# EtherMegaR3.net
KiCad netlist of a schematic drawn in EAGLE
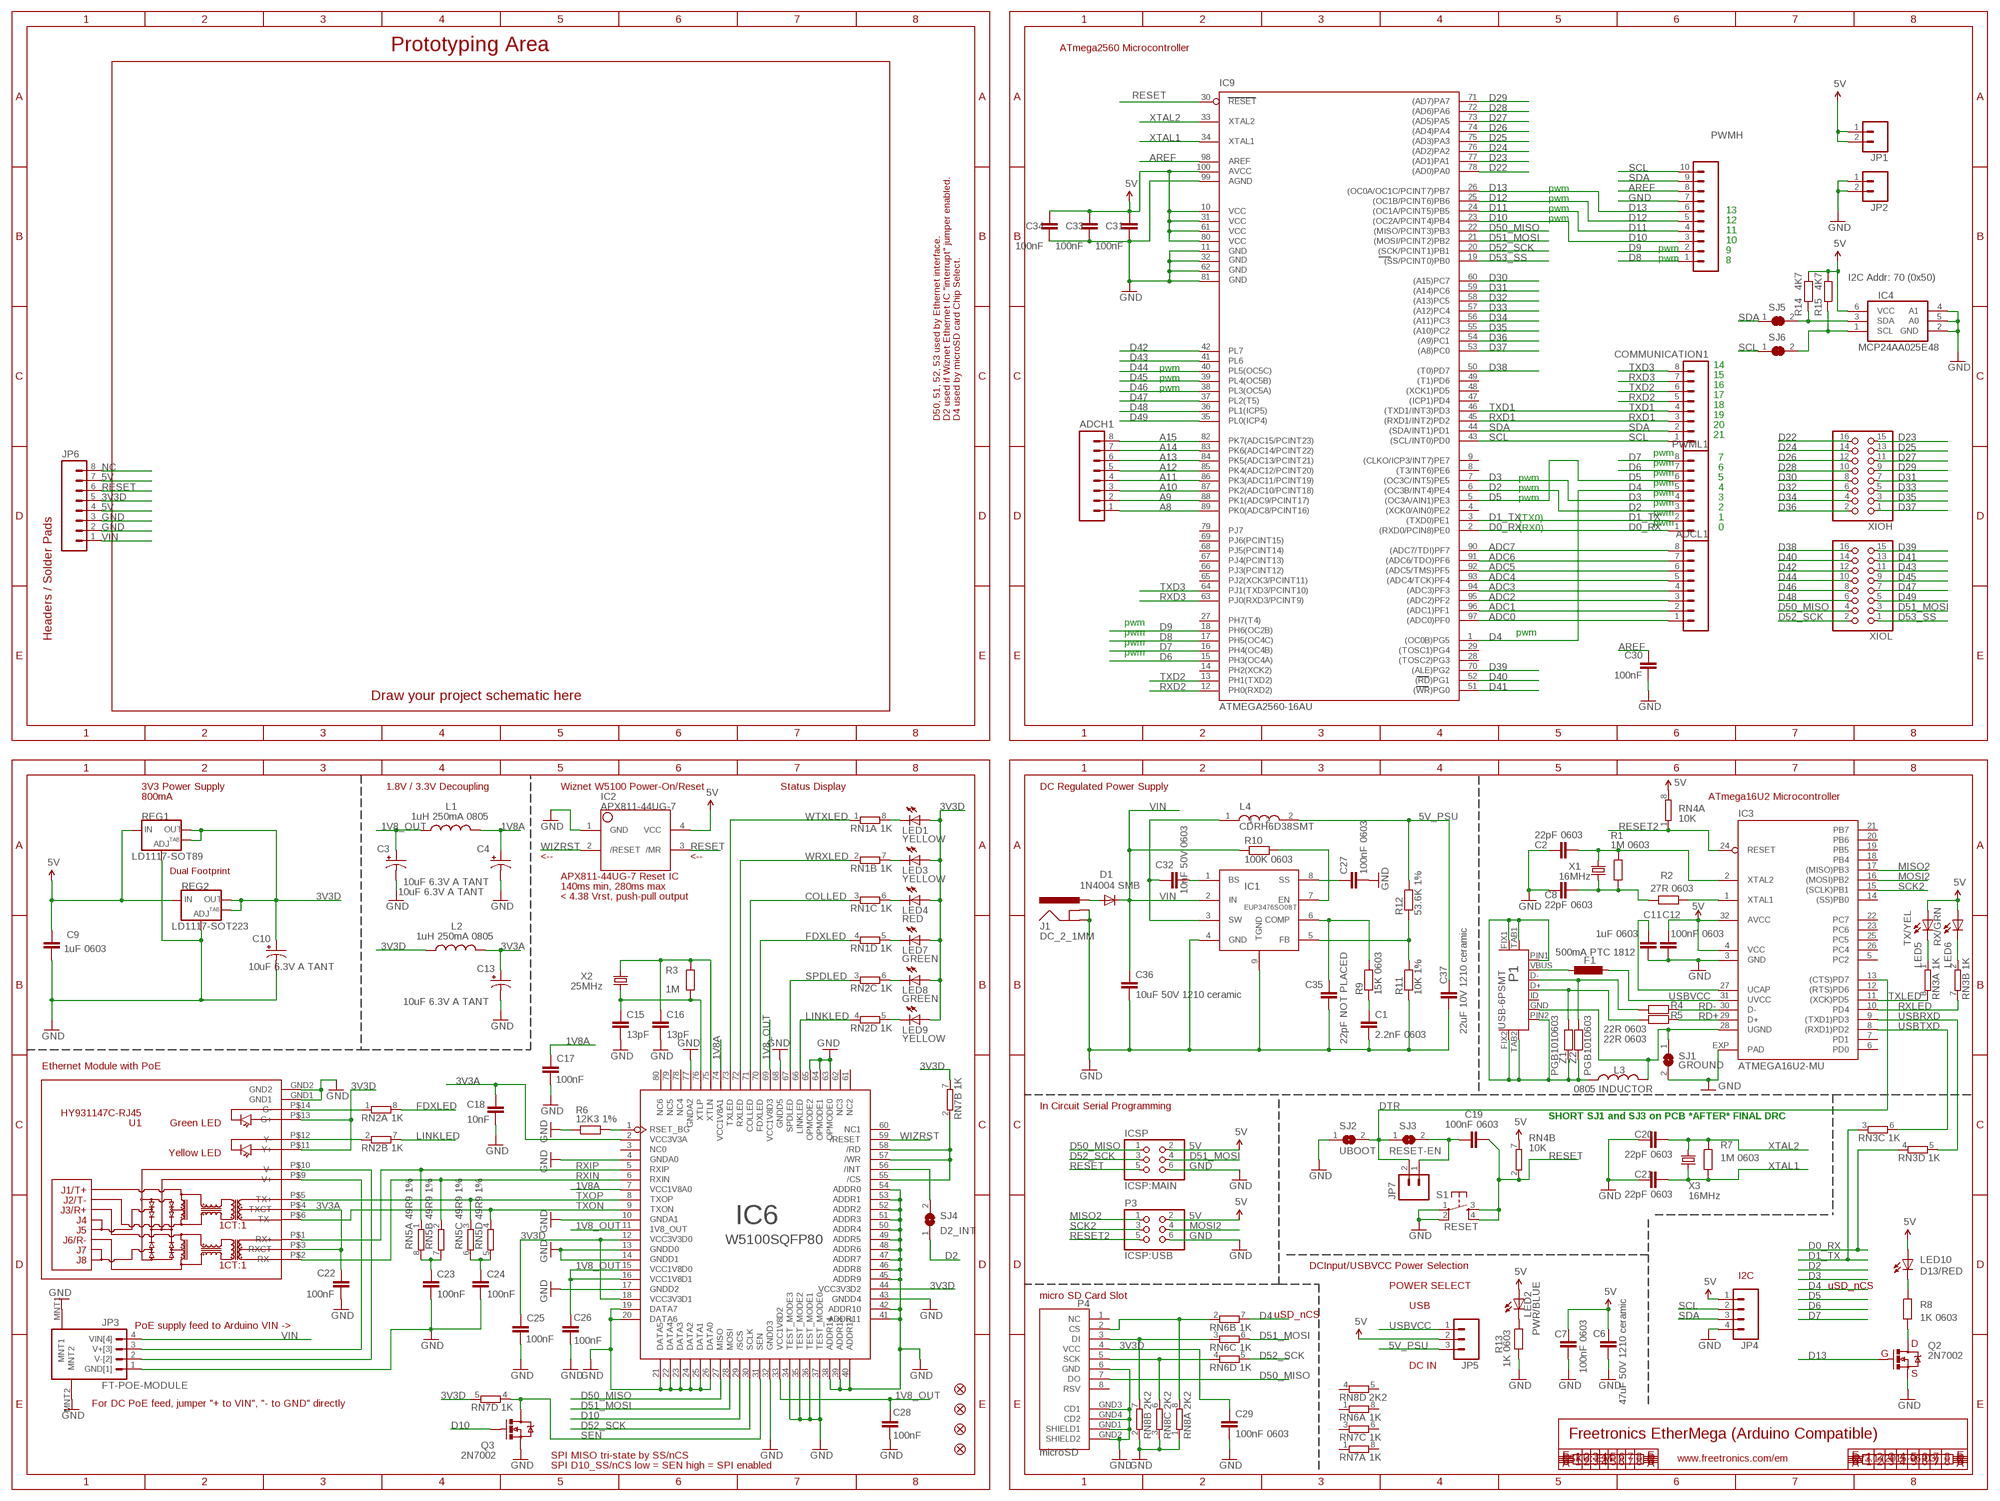
[diagram p0: schematic, sheet 1]

(export (version "E")
  (design (tool "Eeschema 10.0.6"))
  (components
    (comp (ref "ADCH1")
      (value "M08STD")
      (footprint "eagle-import:1X08")
      (libsource (lib "eagle-import") (part "M08STD"))
    )
    (comp (ref "ADCL1")
      (value "M08STD")
      (footprint "eagle-import:1X08")
      (libsource (lib "eagle-import") (part "M08STD"))
    )
    (comp (ref "C1")
      (value "2.2nF 0603")
      (footprint "eagle-import:0603")
      (libsource (lib "eagle-import") (part "CAP0603"))
    )
    (comp (ref "C2")
      (value "22pF 0603")
      (footprint "eagle-import:0603")
      (libsource (lib "eagle-import") (part "CAP0603"))
    )
    (comp (ref "C3")
      (value "10uF 6.3V A TANT")
      (footprint "eagle-import:EIA3216")
      (libsource (lib "eagle-import") (part "CAP_POL1206"))
    )
    (comp (ref "C4")
      (value "10uF 6.3V A TANT")
      (footprint "eagle-import:EIA3216")
      (libsource (lib "eagle-import") (part "CAP_POL1206"))
    )
    (comp (ref "C6")
      (value "47uF 50V 1210 ceramic")
      (footprint "eagle-import:C1210")
      (libsource (lib "eagle-import") (part "C-EUC1210"))
    )
    (comp (ref "C7")
      (value "100nF 0603")
      (footprint "eagle-import:0603")
      (libsource (lib "eagle-import") (part "CAP0603"))
    )
    (comp (ref "C8")
      (value "22pF 0603")
      (footprint "eagle-import:0603")
      (libsource (lib "eagle-import") (part "CAP0603"))
    )
    (comp (ref "C9")
      (value "1uF 0603")
      (footprint "eagle-import:0603")
      (libsource (lib "eagle-import") (part "CAP0603"))
    )
    (comp (ref "C10")
      (value "10uF 6.3V A TANT")
      (footprint "eagle-import:EIA3216")
      (libsource (lib "eagle-import") (part "CAP_POL1206"))
    )
    (comp (ref "C11")
      (value "1uF 0603")
      (footprint "eagle-import:0603")
      (libsource (lib "eagle-import") (part "freetronics-master-v1_CAP0603"))
    )
    (comp (ref "C12")
      (value "100nF 0603")
      (footprint "eagle-import:0603")
      (libsource (lib "eagle-import") (part "CAP0603"))
    )
    (comp (ref "C13")
      (value "10uF 6.3V A TANT")
      (footprint "eagle-import:EIA3216")
      (libsource (lib "eagle-import") (part "CAP_POL1206"))
    )
    (comp (ref "C15")
      (value "13pF")
      (footprint "eagle-import:0603")
      (libsource (lib "eagle-import") (part "CAP0603"))
    )
    (comp (ref "C16")
      (value "13pF")
      (footprint "eagle-import:0603")
      (libsource (lib "eagle-import") (part "CAP0603"))
    )
    (comp (ref "C17")
      (value "100nF")
      (footprint "eagle-import:0603")
      (libsource (lib "eagle-import") (part "CAP0603"))
    )
    (comp (ref "C18")
      (value "10nF")
      (footprint "eagle-import:0603")
      (libsource (lib "eagle-import") (part "CAP0603"))
    )
    (comp (ref "C19")
      (value "100nF 0603")
      (footprint "eagle-import:0603")
      (libsource (lib "eagle-import") (part "CAP0603"))
    )
    (comp (ref "C20")
      (value "22pF 0603")
      (footprint "eagle-import:0603")
      (libsource (lib "eagle-import") (part "CAP0603"))
    )
    (comp (ref "C21")
      (value "22pF 0603")
      (footprint "eagle-import:0603")
      (libsource (lib "eagle-import") (part "CAP0603"))
    )
    (comp (ref "C22")
      (value "100nF")
      (footprint "eagle-import:0603")
      (libsource (lib "eagle-import") (part "CAP0603"))
    )
    (comp (ref "C23")
      (value "100nF")
      (footprint "eagle-import:0603")
      (libsource (lib "eagle-import") (part "CAP0603"))
    )
    (comp (ref "C24")
      (value "100nF")
      (footprint "eagle-import:0603")
      (libsource (lib "eagle-import") (part "CAP0603"))
    )
    (comp (ref "C25")
      (value "100nF")
      (footprint "eagle-import:0603")
      (libsource (lib "eagle-import") (part "CAP0603"))
    )
    (comp (ref "C26")
      (value "100nF")
      (footprint "eagle-import:0603")
      (libsource (lib "eagle-import") (part "CAP0603"))
    )
    (comp (ref "C27")
      (value "100nF 0603")
      (footprint "eagle-import:0603")
      (libsource (lib "eagle-import") (part "CAP0603"))
    )
    (comp (ref "C28")
      (value "100nF")
      (footprint "eagle-import:0603")
      (libsource (lib "eagle-import") (part "CAP0603"))
    )
    (comp (ref "C29")
      (value "100nF 0603")
      (footprint "eagle-import:0603")
      (libsource (lib "eagle-import") (part "CAP0603"))
    )
    (comp (ref "C30")
      (value "100nF")
      (footprint "eagle-import:0603")
      (libsource (lib "eagle-import") (part "CAP0603"))
    )
    (comp (ref "C31")
      (value "100nF")
      (footprint "eagle-import:0603")
      (libsource (lib "eagle-import") (part "CAP0603"))
    )
    (comp (ref "C32")
      (value "10nF 50V 0603")
      (footprint "eagle-import:0603")
      (libsource (lib "eagle-import") (part "CAP0603"))
    )
    (comp (ref "C33")
      (value "100nF")
      (footprint "eagle-import:0603")
      (libsource (lib "eagle-import") (part "CAP0603"))
    )
    (comp (ref "C34")
      (value "100nF")
      (footprint "eagle-import:0603")
      (libsource (lib "eagle-import") (part "CAP0603"))
    )
    (comp (ref "C35")
      (value "22pF NOT PLACED")
      (footprint "eagle-import:0603")
      (libsource (lib "eagle-import") (part "CAP0603"))
    )
    (comp (ref "C36")
      (value "10uF 50V 1210 ceramic")
      (footprint "eagle-import:C1210")
      (libsource (lib "eagle-import") (part "C-EUC1210"))
    )
    (comp (ref "C37")
      (value "22uF 10V 1210 ceramic")
      (footprint "eagle-import:C1210")
      (libsource (lib "eagle-import") (part "C-EUC1210"))
    )
    (comp (ref "COMMUNICATION1")
      (value "M08STD")
      (footprint "eagle-import:1X08")
      (libsource (lib "eagle-import") (part "M08STD"))
    )
    (comp (ref "D1")
      (value "1N4004 SMB")
      (footprint "eagle-import:SMB-DIODE")
      (libsource (lib "eagle-import") (part "DIODESMB"))
    )
    (comp (ref "F1")
      (value "500mA PTC 1812")
      (footprint "eagle-import:L1812")
      (libsource (lib "eagle-import") (part "L-EUL1812"))
    )
    (comp (ref "FID1")
      (value "FIDUCIAL1X2.5")
      (footprint "eagle-import:FIDUCIAL-1X2.5")
      (libsource (lib "eagle-import") (part "FIDUCIAL1X2.5"))
    )
    (comp (ref "FID2")
      (value "FIDUCIAL1X2.5")
      (footprint "eagle-import:FIDUCIAL-1X2.5")
      (libsource (lib "eagle-import") (part "FIDUCIAL1X2.5"))
    )
    (comp (ref "FID3")
      (value "FIDUCIAL1X2.5")
      (footprint "eagle-import:FIDUCIAL-1X2.5")
      (libsource (lib "eagle-import") (part "FIDUCIAL1X2.5"))
    )
    (comp (ref "FID4")
      (value "FIDUCIAL1X2.5")
      (footprint "eagle-import:FIDUCIAL-1X2.5")
      (libsource (lib "eagle-import") (part "FIDUCIAL1X2.5"))
    )
    (comp (ref "IC1")
      (value "EUP3476SO08T")
      (footprint "eagle-import:SO08T")
      (libsource (lib "eagle-import") (part "EUP3476SO08T"))
    )
    (comp (ref "IC2")
      (value "APX811-44UG-7")
      (footprint "eagle-import:SOT143-R")
      (libsource (lib "eagle-import") (part "APX81X-RESET-IC"))
    )
    (comp (ref "IC3")
      (value "ATMEGA16U2-MU")
      (footprint "eagle-import:ATMEL_QFN32")
      (libsource (lib "eagle-import") (part "ATMEL_ATMEGA8U2-MUQFN"))
    )
    (comp (ref "IC4")
      (value "MCP24AA025E48")
      (footprint "eagle-import:SOT23-6")
      (libsource (lib "eagle-import") (part "MCP24AA025E48"))
    )
    (comp (ref "IC6")
      (value "W5100SQFP80")
      (footprint "eagle-import:SQFP80")
      (libsource (lib "eagle-import") (part "W5100SQFP80"))
    )
    (comp (ref "IC9")
      (value "ATMEGA2560-16AU")
      (footprint "eagle-import:TQFP100")
      (libsource (lib "eagle-import") (part "ATMEGAAU1280-16"))
    )
    (comp (ref "ICSP")
      (value "ICSP:MAIN")
      (footprint "eagle-import:2X03")
      (libsource (lib "eagle-import") (part "PINHD-2X3"))
    )
    (comp (ref "J1")
      (value "DC_2_1MM")
      (footprint "eagle-import:POWER_JACK_PTH")
      (libsource (lib "eagle-import") (part "POWER_JACKPTH"))
    )
    (comp (ref "JP1")
      (value "M02PTH")
      (footprint "eagle-import:1X02")
      (libsource (lib "eagle-import") (part "M02PTH"))
    )
    (comp (ref "JP2")
      (value "M02PTH")
      (footprint "eagle-import:1X02")
      (libsource (lib "eagle-import") (part "M02PTH"))
    )
    (comp (ref "JP3")
      (value "FT-POE-MODULE")
      (footprint "eagle-import:FT-POE-MODULE-CLEAN")
      (libsource (lib "eagle-import") (part "FT-POE-MODULE2"))
    )
    (comp (ref "JP4")
      (value "M04PTH")
      (footprint "eagle-import:1X04")
      (libsource (lib "eagle-import") (part "M04PTH"))
    )
    (comp (ref "JP5")
      (value "M03PTH")
      (footprint "eagle-import:1X03")
      (libsource (lib "eagle-import") (part "M03PTH"))
    )
    (comp (ref "JP6")
      (value "M08STD")
      (footprint "eagle-import:1X08")
      (libsource (lib "eagle-import") (part "M08STD"))
    )
    (comp (ref "JP7")
      (value "M02PTH")
      (footprint "eagle-import:1X02")
      (libsource (lib "eagle-import") (part "freetronics-master-v1.1_M02PTH"))
    )
    (comp (ref "L1")
      (value "1uH 250mA 0805")
      (footprint "eagle-import:L2012C")
      (libsource (lib "eagle-import") (part "L-USL2012C"))
    )
    (comp (ref "L2")
      (value "1uH 250mA 0805")
      (footprint "eagle-import:L2012C")
      (libsource (lib "eagle-import") (part "L-USL2012C"))
    )
    (comp (ref "L3")
      (value "0805 INDUCTOR")
      (footprint "eagle-import:0805-LARGE")
      (libsource (lib "eagle-import") (part "INDUCTOR0805-LARGE"))
    )
    (comp (ref "L4")
      (value "CDRH6D38SMT")
      (footprint "eagle-import:CDRH")
      (libsource (lib "eagle-import") (part "CDRH6D38SMT"))
    )
    (comp (ref "LED1")
      (value "YELLOW")
      (footprint "eagle-import:LED-0603")
      (libsource (lib "eagle-import") (part "LED0603"))
    )
    (comp (ref "LED2")
      (value "PWR/BLUE")
      (footprint "eagle-import:LED-0603")
      (libsource (lib "eagle-import") (part "LED0603"))
    )
    (comp (ref "LED3")
      (value "YELLOW")
      (footprint "eagle-import:LED-0603")
      (libsource (lib "eagle-import") (part "LED0603"))
    )
    (comp (ref "LED4")
      (value "RED")
      (footprint "eagle-import:LED-0603")
      (libsource (lib "eagle-import") (part "LED0603"))
    )
    (comp (ref "LED5")
      (value "TX/YEL")
      (footprint "eagle-import:LED-0603")
      (libsource (lib "eagle-import") (part "LED0603"))
    )
    (comp (ref "LED6")
      (value "RX/GRN")
      (footprint "eagle-import:LED-0603")
      (libsource (lib "eagle-import") (part "LED0603"))
    )
    (comp (ref "LED7")
      (value "GREEN")
      (footprint "eagle-import:LED-0603")
      (libsource (lib "eagle-import") (part "LED0603"))
    )
    (comp (ref "LED8")
      (value "GREEN")
      (footprint "eagle-import:LED-0603")
      (libsource (lib "eagle-import") (part "LED0603"))
    )
    (comp (ref "LED9")
      (value "YELLOW")
      (footprint "eagle-import:LED-0603")
      (libsource (lib "eagle-import") (part "LED0603"))
    )
    (comp (ref "LED10")
      (value "D13/RED")
      (footprint "eagle-import:LED-0603")
      (libsource (lib "eagle-import") (part "LED0603"))
    )
    (comp (ref "P1")
      (value "USB-6PSMT")
      (footprint "eagle-import:USB-MICROB-MB05PMXX")
      (libsource (lib "eagle-import") (part "USB-6PSMT"))
    )
    (comp (ref "P3")
      (value "ICSP:USB")
      (footprint "eagle-import:2X03")
      (libsource (lib "eagle-import") (part "PINHD-2X3"))
    )
    (comp (ref "P4")
      (value "microSD")
      (footprint "eagle-import:MOLEX-SD-500901-003")
      (libsource (lib "eagle-import") (part "USD-SOCKETHINGE"))
    )
    (comp (ref "PWMH")
      (value "M100.1")
      (footprint "eagle-import:1X10")
      (libsource (lib "eagle-import") (part "M100.1"))
    )
    (comp (ref "PWML1")
      (value "M08STD")
      (footprint "eagle-import:1X08")
      (libsource (lib "eagle-import") (part "M08STD"))
    )
    (comp (ref "Q2")
      (value "2N7002")
      (footprint "eagle-import:SOT23-3")
      (libsource (lib "eagle-import") (part "MOSFET-NCHANNELSMD"))
    )
    (comp (ref "Q3")
      (value "2N7002")
      (footprint "eagle-import:SOT23-3")
      (libsource (lib "eagle-import") (part "MOSFET-NCHANNELSMD"))
    )
    (comp (ref "R1")
      (value "1M 0603")
      (footprint "eagle-import:0603")
      (libsource (lib "eagle-import") (part "freetronics-marc_RESISTOR0603"))
    )
    (comp (ref "R2")
      (value "27R 0603")
      (footprint "eagle-import:0603")
      (libsource (lib "eagle-import") (part "freetronics-marc_RESISTOR0603"))
    )
    (comp (ref "R3")
      (value "1M")
      (footprint "eagle-import:0603")
      (libsource (lib "eagle-import") (part "freetronics-marc_RESISTOR0603"))
    )
    (comp (ref "R4")
      (value "22R 0603")
      (footprint "eagle-import:0603")
      (libsource (lib "eagle-import") (part "freetronics-marc_RESISTOR0603"))
    )
    (comp (ref "R5")
      (value "22R 0603")
      (footprint "eagle-import:0603")
      (libsource (lib "eagle-import") (part "freetronics-marc_RESISTOR0603"))
    )
    (comp (ref "R6")
      (value "12K3 1%")
      (footprint "eagle-import:0603")
      (libsource (lib "eagle-import") (part "freetronics-marc_RESISTOR0603"))
    )
    (comp (ref "R7")
      (value "1M 0603")
      (footprint "eagle-import:0603")
      (libsource (lib "eagle-import") (part "freetronics-marc_RESISTOR0603"))
    )
    (comp (ref "R8")
      (value "1K 0603")
      (footprint "eagle-import:0603")
      (libsource (lib "eagle-import") (part "freetronics-marc_RESISTOR0603"))
    )
    (comp (ref "R9")
      (value "15K 0603")
      (footprint "eagle-import:0603")
      (libsource (lib "eagle-import") (part "freetronics-original_RESISTOR0603"))
    )
    (comp (ref "R10")
      (value "100K 0603")
      (footprint "eagle-import:0603")
      (libsource (lib "eagle-import") (part "freetronics-original_RESISTOR0603"))
    )
    (comp (ref "R11")
      (value "10K 1%")
      (footprint "eagle-import:0603")
      (libsource (lib "eagle-import") (part "freetronics-original_RESISTOR0603"))
    )
    (comp (ref "R12")
      (value "53.6K 1%")
      (footprint "eagle-import:0603")
      (libsource (lib "eagle-import") (part "freetronics-original_RESISTOR0603"))
    )
    (comp (ref "R13")
      (value "1K 0603")
      (footprint "eagle-import:0603")
      (libsource (lib "eagle-import") (part "freetronics-marc_RESISTOR0603"))
    )
    (comp (ref "R14")
      (value "4K7")
      (footprint "eagle-import:0603")
      (libsource (lib "eagle-import") (part "freetronics-master-v1.1_RESISTOR0603"))
    )
    (comp (ref "R15")
      (value "4K7")
      (footprint "eagle-import:0603")
      (libsource (lib "eagle-import") (part "freetronics-master-v1.1_RESISTOR0603"))
    )
    (comp (ref "REG1")
      (value "LD1117-SOT89")
      (footprint "eagle-import:SOT89")
      (libsource (lib "eagle-import") (part "V_REG_LM1117SOT89"))
    )
    (comp (ref "REG2")
      (value "LD1117-SOT223")
      (footprint "eagle-import:SOT223")
      (libsource (lib "eagle-import") (part "V_REG_LM1117SOT223"))
    )
    (comp (ref "RN1")
      (value "1K")
      (footprint "eagle-import:CAY16")
      (libsource (lib "eagle-import") (part "4R-NCAY16"))
    )
    (comp (ref "RN2")
      (value "1K")
      (footprint "eagle-import:CAY16")
      (libsource (lib "eagle-import") (part "4R-NCAY16"))
    )
    (comp (ref "RN3")
      (value "1K")
      (footprint "eagle-import:CAY16")
      (libsource (lib "eagle-import") (part "4R-NCAY16"))
    )
    (comp (ref "RN4")
      (value "10K")
      (footprint "eagle-import:CAY16")
      (libsource (lib "eagle-import") (part "4R-NCAY16"))
    )
    (comp (ref "RN5")
      (value "49R9 1%")
      (footprint "eagle-import:CAY16")
      (libsource (lib "eagle-import") (part "4R-NCAY16"))
    )
    (comp (ref "RN6")
      (value "1K")
      (footprint "eagle-import:CAY16")
      (libsource (lib "eagle-import") (part "4R-NCAY16"))
    )
    (comp (ref "RN7")
      (value "1K")
      (footprint "eagle-import:CAY16")
      (libsource (lib "eagle-import") (part "4R-NCAY16"))
    )
    (comp (ref "RN8")
      (value "2K2")
      (footprint "eagle-import:CAY16")
      (libsource (lib "eagle-import") (part "4R-NCAY16"))
    )
    (comp (ref "S1")
      (value "RESET")
      (footprint "eagle-import:TACTILE_SWITCH_SMD")
      (libsource (lib "eagle-import") (part "TAC_SWITCHSMD"))
    )
    (comp (ref "SJ1")
      (value "GROUND")
      (footprint "eagle-import:SJ")
      (libsource (lib "eagle-import") (part "SJ"))
    )
    (comp (ref "SJ2")
      (value "UBOOT")
      (footprint "eagle-import:SJ")
      (libsource (lib "eagle-import") (part "SJ"))
    )
    (comp (ref "SJ3")
      (value "RESET-EN")
      (footprint "eagle-import:SJ")
      (libsource (lib "eagle-import") (part "SJ"))
    )
    (comp (ref "SJ4")
      (value "D2_INT")
      (footprint "eagle-import:SJ")
      (libsource (lib "eagle-import") (part "SJ"))
    )
    (comp (ref "SJ5")
      (value "SJCN")
      (footprint "eagle-import:SJC")
      (libsource (lib "eagle-import") (part "SJCN"))
    )
    (comp (ref "SJ6")
      (value "SJCN")
      (footprint "eagle-import:SJC")
      (libsource (lib "eagle-import") (part "SJCN"))
    )
    (comp (ref "U1")
      (value "HY931147C-RJ45")
      (footprint "eagle-import:HY931147C")
      (libsource (lib "eagle-import") (part "HY931147C-RJ45"))
    )
    (comp (ref "X1")
      (value "16MHz")
      (footprint "eagle-import:HC49U-V")
      (libsource (lib "eagle-import") (part "CRYSTALHC49UV"))
    )
    (comp (ref "X2")
      (value "25MHz")
      (footprint "eagle-import:HC49U-V")
      (libsource (lib "eagle-import") (part "CRYSTALHC49UV"))
    )
    (comp (ref "X3")
      (value "16MHz")
      (footprint "eagle-import:HC49U-V")
      (libsource (lib "eagle-import") (part "CRYSTALHC49UV"))
    )
    (comp (ref "XIOH")
      (value "PINHD-2X8")
      (footprint "eagle-import:2X08")
      (libsource (lib "eagle-import") (part "PINHD-2X8"))
    )
    (comp (ref "XIOL")
      (value "PINHD-2X8")
      (footprint "eagle-import:2X08")
      (libsource (lib "eagle-import") (part "PINHD-2X8"))
    )
    (comp (ref "Z1")
      (value "PGB1010603")
      (footprint "eagle-import:0603")
      (libsource (lib "eagle-import") (part "RESISTOR0603"))
    )
    (comp (ref "Z2")
      (value "PGB1010603")
      (footprint "eagle-import:0603")
      (libsource (lib "eagle-import") (part "RESISTOR0603"))
    )
  )
  (nets
    (net (code "1") (name "/1V8A") (class "Default")
      (node (ref "C17") (pin "1") (pinfunction "1_1") (pintype "passive"))
      (node (ref "C4") (pin "A") (pinfunction "+_A") (pintype "passive"))
      (node (ref "IC6") (pin "7") (pinfunction "VCC1V8A0_7") (pintype "bidirectional"))
      (node (ref "IC6") (pin "74") (pinfunction "VCC1V8A1_74") (pintype "bidirectional"))
      (node (ref "L1") (pin "2") (pinfunction "2_2") (pintype "passive"))
    )
    (net (code "2") (name "/1V8_OUT") (class "Default")
      (node (ref "C26") (pin "1") (pinfunction "1_1") (pintype "passive"))
      (node (ref "C28") (pin "1") (pinfunction "1_1") (pintype "passive"))
      (node (ref "C3") (pin "A") (pinfunction "+_A") (pintype "passive"))
      (node (ref "IC6") (pin "11") (pinfunction "1V8_OUT_11") (pintype "bidirectional"))
      (node (ref "IC6") (pin "15") (pinfunction "VCC1V8D0_15") (pintype "bidirectional"))
      (node (ref "IC6") (pin "16") (pinfunction "VCC1V8D1_16") (pintype "bidirectional"))
      (node (ref "IC6") (pin "33") (pinfunction "VCC1V8D2_33") (pintype "bidirectional"))
      (node (ref "IC6") (pin "69") (pinfunction "VCC1V8D3_69") (pintype "bidirectional"))
      (node (ref "L1") (pin "1") (pinfunction "1_1") (pintype "passive"))
    )
    (net (code "3") (name "/3V3A") (class "Default")
      (node (ref "C13") (pin "A") (pinfunction "+_A") (pintype "passive"))
      (node (ref "C18") (pin "1") (pinfunction "1_1") (pintype "passive"))
      (node (ref "C22") (pin "1") (pinfunction "1_1") (pintype "passive"))
      (node (ref "IC6") (pin "2") (pinfunction "VCC3V3A_2") (pintype "bidirectional"))
      (node (ref "L2") (pin "2") (pinfunction "2_2") (pintype "passive"))
      (node (ref "U1") (pin "P$3") (pinfunction "RXCT_P$3") (pintype "bidirectional"))
      (node (ref "U1") (pin "P$4") (pinfunction "TXCT_P$4") (pintype "bidirectional"))
    )
    (net (code "4") (name "/3V3D") (class "Default")
      (node (ref "C10") (pin "A") (pinfunction "+_A") (pintype "passive"))
      (node (ref "C25") (pin "1") (pinfunction "1_1") (pintype "passive"))
      (node (ref "C29") (pin "1") (pinfunction "1_1") (pintype "passive"))
      (node (ref "IC6") (pin "12") (pinfunction "VCC3V3D0_12") (pintype "bidirectional"))
      (node (ref "IC6") (pin "18") (pinfunction "VCC3V3D1_18") (pintype "bidirectional"))
      (node (ref "IC6") (pin "44") (pinfunction "VCC3V3D2_44") (pintype "bidirectional"))
      (node (ref "JP6") (pin "5") (pinfunction "5_5") (pintype "passive"))
      (node (ref "L2") (pin "1") (pinfunction "1_1") (pintype "passive"))
      (node (ref "LED1") (pin "A") (pinfunction "A_A") (pintype "passive"))
      (node (ref "LED3") (pin "A") (pinfunction "A_A") (pintype "passive"))
      (node (ref "LED4") (pin "A") (pinfunction "A_A") (pintype "passive"))
      (node (ref "LED7") (pin "A") (pinfunction "A_A") (pintype "passive"))
      (node (ref "LED8") (pin "A") (pinfunction "A_A") (pintype "passive"))
      (node (ref "LED9") (pin "A") (pinfunction "A_A") (pintype "passive"))
      (node (ref "P4") (pin "4") (pinfunction "VCC_4") (pintype "bidirectional"))
      (node (ref "REG1") (pin "2") (pinfunction "OUT_2") (pintype "output"))
      (node (ref "REG1") (pin "4") (pinfunction "OUT_4") (pintype "output"))
      (node (ref "REG2") (pin "2") (pinfunction "OUT_2") (pintype "output"))
      (node (ref "REG2") (pin "4") (pinfunction "OUT_4") (pintype "output"))
      (node (ref "RN7") (pin "5") (pinfunction "2_5") (pintype "passive"))
      (node (ref "RN7") (pin "7") (pinfunction "2_7") (pintype "passive"))
      (node (ref "U1") (pin "P$11") (pinfunction "Y+_P$11") (pintype "bidirectional"))
      (node (ref "U1") (pin "P$13") (pinfunction "G+_P$13") (pintype "bidirectional"))
    )
    (net (code "5") (name "/5V_PSU") (class "Default")
      (node (ref "C37") (pin "1") (pinfunction "1_1") (pintype "passive"))
      (node (ref "JP5") (pin "3") (pinfunction "3_3") (pintype "passive"))
      (node (ref "L4") (pin "2") (pinfunction "2_2") (pintype "bidirectional"))
      (node (ref "R12") (pin "2") (pinfunction "2_2") (pintype "passive"))
    )
    (net (code "6") (name "/A8") (class "Default")
      (node (ref "ADCH1") (pin "1") (pinfunction "1_1") (pintype "passive"))
      (node (ref "IC9") (pin "89") (pinfunction "PK0(ADC8/PCINT16)_89") (pintype "bidirectional"))
    )
    (net (code "7") (name "/A9") (class "Default")
      (node (ref "ADCH1") (pin "2") (pinfunction "2_2") (pintype "passive"))
      (node (ref "IC9") (pin "88") (pinfunction "PK1(ADC9/PCINT17)_88") (pintype "bidirectional"))
    )
    (net (code "8") (name "/A10") (class "Default")
      (node (ref "ADCH1") (pin "3") (pinfunction "3_3") (pintype "passive"))
      (node (ref "IC9") (pin "87") (pinfunction "PK2(ADC10/PCINT18)_87") (pintype "bidirectional"))
    )
    (net (code "9") (name "/A11") (class "Default")
      (node (ref "ADCH1") (pin "4") (pinfunction "4_4") (pintype "passive"))
      (node (ref "IC9") (pin "86") (pinfunction "PK3(ADC11/PCINT19)_86") (pintype "bidirectional"))
    )
    (net (code "10") (name "/A12") (class "Default")
      (node (ref "ADCH1") (pin "5") (pinfunction "5_5") (pintype "passive"))
      (node (ref "IC9") (pin "85") (pinfunction "PK4(ADC12/PCINT20)_85") (pintype "bidirectional"))
    )
    (net (code "11") (name "/A13") (class "Default")
      (node (ref "ADCH1") (pin "6") (pinfunction "6_6") (pintype "passive"))
      (node (ref "IC9") (pin "84") (pinfunction "PK5(ADC13/PCINT21)_84") (pintype "bidirectional"))
    )
    (net (code "12") (name "/A14") (class "Default")
      (node (ref "ADCH1") (pin "7") (pinfunction "7_7") (pintype "passive"))
      (node (ref "IC9") (pin "83") (pinfunction "PK6(ADC14/PCINT22)_83") (pintype "bidirectional"))
    )
    (net (code "13") (name "/A15") (class "Default")
      (node (ref "ADCH1") (pin "8") (pinfunction "8_8") (pintype "passive"))
      (node (ref "IC9") (pin "82") (pinfunction "PK7(ADC15/PCINT23)_82") (pintype "bidirectional"))
    )
    (net (code "14") (name "/ADC0") (class "Default")
      (node (ref "ADCL1") (pin "1") (pinfunction "1_1") (pintype "passive"))
      (node (ref "IC9") (pin "97") (pinfunction "(ADC0)PF0_97") (pintype "bidirectional"))
    )
    (net (code "15") (name "/ADC1") (class "Default")
      (node (ref "ADCL1") (pin "2") (pinfunction "2_2") (pintype "passive"))
      (node (ref "IC9") (pin "96") (pinfunction "(ADC1)PF1_96") (pintype "bidirectional"))
    )
    (net (code "16") (name "/ADC2") (class "Default")
      (node (ref "ADCL1") (pin "3") (pinfunction "3_3") (pintype "passive"))
      (node (ref "IC9") (pin "95") (pinfunction "(ADC2)PF2_95") (pintype "bidirectional"))
    )
    (net (code "17") (name "/ADC3") (class "Default")
      (node (ref "ADCL1") (pin "4") (pinfunction "4_4") (pintype "passive"))
      (node (ref "IC9") (pin "94") (pinfunction "(ADC3)PF3_94") (pintype "bidirectional"))
    )
    (net (code "18") (name "/ADC4") (class "Default")
      (node (ref "ADCL1") (pin "5") (pinfunction "5_5") (pintype "passive"))
      (node (ref "IC9") (pin "93") (pinfunction "(ADC4/TCK)PF4_93") (pintype "bidirectional"))
    )
    (net (code "19") (name "/ADC5") (class "Default")
      (node (ref "ADCL1") (pin "6") (pinfunction "6_6") (pintype "passive"))
      (node (ref "IC9") (pin "92") (pinfunction "(ADC5/TMS)PF5_92") (pintype "bidirectional"))
    )
    (net (code "20") (name "/ADC6") (class "Default")
      (node (ref "ADCL1") (pin "7") (pinfunction "7_7") (pintype "passive"))
      (node (ref "IC9") (pin "91") (pinfunction "(ADC6/TDO)PF6_91") (pintype "bidirectional"))
    )
    (net (code "21") (name "/ADC7") (class "Default")
      (node (ref "ADCL1") (pin "8") (pinfunction "8_8") (pintype "passive"))
      (node (ref "IC9") (pin "90") (pinfunction "(ADC7/TDI)PF7_90") (pintype "bidirectional"))
    )
    (net (code "22") (name "/AREF") (class "Default")
      (node (ref "C30") (pin "1") (pinfunction "1_1") (pintype "passive"))
      (node (ref "IC9") (pin "98") (pinfunction "AREF_98") (pintype "bidirectional"))
      (node (ref "PWMH") (pin "8") (pinfunction "8_8") (pintype "passive"))
    )
    (net (code "23") (name "/COLLED") (class "Default")
      (node (ref "IC6") (pin "71") (pinfunction "COLLED_71") (pintype "bidirectional"))
      (node (ref "RN1") (pin "3") (pinfunction "1_3") (pintype "passive"))
    )
    (net (code "24") (name "/D0_RX") (class "Default")
      (node (ref "IC9") (pin "2") (pinfunction "(RXD0/PCIN8)PE0_2") (pintype "bidirectional"))
      (node (ref "PWML1") (pin "1") (pinfunction "1_1") (pintype "passive"))
      (node (ref "RN3") (pin "4") (pinfunction "1_4") (pintype "passive"))
    )
    (net (code "25") (name "/D1_TX") (class "Default")
      (node (ref "IC9") (pin "3") (pinfunction "(TXD0)PE1_3") (pintype "bidirectional"))
      (node (ref "PWML1") (pin "2") (pinfunction "2_2") (pintype "passive"))
      (node (ref "RN3") (pin "3") (pinfunction "1_3") (pintype "passive"))
    )
    (net (code "26") (name "/D2") (class "Default")
      (node (ref "IC9") (pin "6") (pinfunction "(OC3B/INT4)PE4_6") (pintype "bidirectional"))
      (node (ref "PWML1") (pin "3") (pinfunction "3_3") (pintype "passive"))
      (node (ref "SJ4") (pin "1") (pinfunction "1_1") (pintype "passive"))
    )
    (net (code "27") (name "/D3") (class "Default")
      (node (ref "IC9") (pin "7") (pinfunction "(OC3C/INT5)PE5_7") (pintype "bidirectional"))
      (node (ref "PWML1") (pin "4") (pinfunction "4_4") (pintype "passive"))
    )
    (net (code "28") (name "/D4") (class "Default")
      (node (ref "IC9") (pin "1") (pinfunction "(OC0B)PG5_1") (pintype "bidirectional"))
      (node (ref "PWML1") (pin "5") (pinfunction "5_5") (pintype "passive"))
      (node (ref "RN6") (pin "7") (pinfunction "2_7") (pintype "passive"))
    )
    (net (code "29") (name "/D5") (class "Default")
      (node (ref "IC9") (pin "5") (pinfunction "(OC3A/AIN1)PE3_5") (pintype "bidirectional"))
      (node (ref "PWML1") (pin "6") (pinfunction "6_6") (pintype "passive"))
    )
    (net (code "30") (name "/D6") (class "Default")
      (node (ref "IC9") (pin "15") (pinfunction "PH3(OC4A)_15") (pintype "bidirectional"))
      (node (ref "PWML1") (pin "7") (pinfunction "7_7") (pintype "passive"))
    )
    (net (code "31") (name "/D7") (class "Default")
      (node (ref "IC9") (pin "16") (pinfunction "PH4(OC4B)_16") (pintype "bidirectional"))
      (node (ref "PWML1") (pin "8") (pinfunction "8_8") (pintype "passive"))
    )
    (net (code "32") (name "/D8") (class "Default")
      (node (ref "IC9") (pin "17") (pinfunction "PH5(OC4C)_17") (pintype "bidirectional"))
      (node (ref "PWMH") (pin "1") (pinfunction "1_1") (pintype "passive"))
    )
    (net (code "33") (name "/D9") (class "Default")
      (node (ref "IC9") (pin "18") (pinfunction "PH6(OC2B)_18") (pintype "bidirectional"))
      (node (ref "PWMH") (pin "2") (pinfunction "2_2") (pintype "passive"))
    )
    (net (code "34") (name "/D10") (class "Default")
      (node (ref "IC6") (pin "29") (pinfunction "/SCS_29") (pintype "bidirectional"))
      (node (ref "IC9") (pin "23") (pinfunction "(OC2A/PCINT4)PB4_23") (pintype "bidirectional"))
      (node (ref "PWMH") (pin "3") (pinfunction "3_3") (pintype "passive"))
      (node (ref "Q3") (pin "1") (pinfunction "G_1") (pintype "passive"))
    )
    (net (code "35") (name "/D11") (class "Default")
      (node (ref "IC9") (pin "24") (pinfunction "(OC1A/PCINT5)PB5_24") (pintype "bidirectional"))
      (node (ref "PWMH") (pin "4") (pinfunction "4_4") (pintype "passive"))
    )
    (net (code "36") (name "/D12") (class "Default")
      (node (ref "IC9") (pin "25") (pinfunction "(OC1B/PCINT6)PB6_25") (pintype "bidirectional"))
      (node (ref "PWMH") (pin "5") (pinfunction "5_5") (pintype "passive"))
    )
    (net (code "37") (name "/D13") (class "Default")
      (node (ref "IC9") (pin "26") (pinfunction "(OC0A/OC1C/PCINT7)PB7_26") (pintype "bidirectional"))
      (node (ref "PWMH") (pin "6") (pinfunction "6_6") (pintype "passive"))
      (node (ref "Q2") (pin "1") (pinfunction "G_1") (pintype "passive"))
    )
    (net (code "38") (name "/D22") (class "Default")
      (node (ref "IC9") (pin "78") (pinfunction "(AD0)PA0_78") (pintype "bidirectional"))
      (node (ref "XIOH") (pin "16") (pinfunction "16_16") (pintype "passive"))
    )
    (net (code "39") (name "/D23") (class "Default")
      (node (ref "IC9") (pin "77") (pinfunction "(AD1)PA1_77") (pintype "bidirectional"))
      (node (ref "XIOH") (pin "15") (pinfunction "15_15") (pintype "passive"))
    )
    (net (code "40") (name "/D24") (class "Default")
      (node (ref "IC9") (pin "76") (pinfunction "(AD2)PA2_76") (pintype "bidirectional"))
      (node (ref "XIOH") (pin "14") (pinfunction "14_14") (pintype "passive"))
    )
    (net (code "41") (name "/D25") (class "Default")
      (node (ref "IC9") (pin "75") (pinfunction "(AD3)PA3_75") (pintype "bidirectional"))
      (node (ref "XIOH") (pin "13") (pinfunction "13_13") (pintype "passive"))
    )
    (net (code "42") (name "/D26") (class "Default")
      (node (ref "IC9") (pin "74") (pinfunction "(AD4)PA4_74") (pintype "bidirectional"))
      (node (ref "XIOH") (pin "12") (pinfunction "12_12") (pintype "passive"))
    )
    (net (code "43") (name "/D27") (class "Default")
      (node (ref "IC9") (pin "73") (pinfunction "(AD5)PA5_73") (pintype "bidirectional"))
      (node (ref "XIOH") (pin "11") (pinfunction "11_11") (pintype "passive"))
    )
    (net (code "44") (name "/D28") (class "Default")
      (node (ref "IC9") (pin "72") (pinfunction "(AD6)PA6_72") (pintype "bidirectional"))
      (node (ref "XIOH") (pin "10") (pinfunction "10_10") (pintype "passive"))
    )
    (net (code "45") (name "/D29") (class "Default")
      (node (ref "IC9") (pin "71") (pinfunction "(AD7)PA7_71") (pintype "bidirectional"))
      (node (ref "XIOH") (pin "9") (pinfunction "9_9") (pintype "passive"))
    )
    (net (code "46") (name "/D30") (class "Default")
      (node (ref "IC9") (pin "60") (pinfunction "(A15)PC7_60") (pintype "bidirectional"))
      (node (ref "XIOH") (pin "8") (pinfunction "8_8") (pintype "passive"))
    )
    (net (code "47") (name "/D31") (class "Default")
      (node (ref "IC9") (pin "59") (pinfunction "(A14)PC6_59") (pintype "bidirectional"))
      (node (ref "XIOH") (pin "7") (pinfunction "7_7") (pintype "passive"))
    )
    (net (code "48") (name "/D32") (class "Default")
      (node (ref "IC9") (pin "58") (pinfunction "(A13)PC5_58") (pintype "bidirectional"))
      (node (ref "XIOH") (pin "6") (pinfunction "6_6") (pintype "passive"))
    )
    (net (code "49") (name "/D33") (class "Default")
      (node (ref "IC9") (pin "57") (pinfunction "(A12)PC4_57") (pintype "bidirectional"))
      (node (ref "XIOH") (pin "5") (pinfunction "5_5") (pintype "passive"))
    )
    (net (code "50") (name "/D34") (class "Default")
      (node (ref "IC9") (pin "56") (pinfunction "(A11)PC3_56") (pintype "bidirectional"))
      (node (ref "XIOH") (pin "4") (pinfunction "4_4") (pintype "passive"))
    )
    (net (code "51") (name "/D35") (class "Default")
      (node (ref "IC9") (pin "55") (pinfunction "(A10)PC2_55") (pintype "bidirectional"))
      (node (ref "XIOH") (pin "3") (pinfunction "3_3") (pintype "passive"))
    )
    (net (code "52") (name "/D36") (class "Default")
      (node (ref "IC9") (pin "54") (pinfunction "(A9)PC1_54") (pintype "bidirectional"))
      (node (ref "XIOH") (pin "2") (pinfunction "2_2") (pintype "passive"))
    )
    (net (code "53") (name "/D37") (class "Default")
      (node (ref "IC9") (pin "53") (pinfunction "(A8)PC0_53") (pintype "bidirectional"))
      (node (ref "XIOH") (pin "1") (pinfunction "1_1") (pintype "passive"))
    )
    (net (code "54") (name "/D38") (class "Default")
      (node (ref "IC9") (pin "50") (pinfunction "(T0)PD7_50") (pintype "bidirectional"))
      (node (ref "XIOL") (pin "16") (pinfunction "16_16") (pintype "passive"))
    )
    (net (code "55") (name "/D39") (class "Default")
      (node (ref "IC9") (pin "70") (pinfunction "(ALE)PG2_70") (pintype "bidirectional"))
      (node (ref "XIOL") (pin "15") (pinfunction "15_15") (pintype "passive"))
    )
    (net (code "56") (name "/D40") (class "Default")
      (node (ref "IC9") (pin "52") (pinfunction "(RD)PG1_52") (pintype "bidirectional"))
      (node (ref "XIOL") (pin "14") (pinfunction "14_14") (pintype "passive"))
    )
    (net (code "57") (name "/D41") (class "Default")
      (node (ref "IC9") (pin "51") (pinfunction "(WR)PG0_51") (pintype "bidirectional"))
      (node (ref "XIOL") (pin "13") (pinfunction "13_13") (pintype "passive"))
    )
    (net (code "58") (name "/D42") (class "Default")
      (node (ref "IC9") (pin "42") (pinfunction "PL7_42") (pintype "bidirectional"))
      (node (ref "XIOL") (pin "12") (pinfunction "12_12") (pintype "passive"))
    )
    (net (code "59") (name "/D43") (class "Default")
      (node (ref "IC9") (pin "41") (pinfunction "PL6_41") (pintype "bidirectional"))
      (node (ref "XIOL") (pin "11") (pinfunction "11_11") (pintype "passive"))
    )
    (net (code "60") (name "/D44") (class "Default")
      (node (ref "IC9") (pin "40") (pinfunction "PL5(OC5C)_40") (pintype "bidirectional"))
      (node (ref "XIOL") (pin "10") (pinfunction "10_10") (pintype "passive"))
    )
    (net (code "61") (name "/D45") (class "Default")
      (node (ref "IC9") (pin "39") (pinfunction "PL4(OC5B)_39") (pintype "bidirectional"))
      (node (ref "XIOL") (pin "9") (pinfunction "9_9") (pintype "passive"))
    )
    (net (code "62") (name "/D46") (class "Default")
      (node (ref "IC9") (pin "38") (pinfunction "PL3(OC5A)_38") (pintype "bidirectional"))
      (node (ref "XIOL") (pin "8") (pinfunction "8_8") (pintype "passive"))
    )
    (net (code "63") (name "/D47") (class "Default")
      (node (ref "IC9") (pin "37") (pinfunction "PL2(T5)_37") (pintype "bidirectional"))
      (node (ref "XIOL") (pin "7") (pinfunction "7_7") (pintype "passive"))
    )
    (net (code "64") (name "/D48") (class "Default")
      (node (ref "IC9") (pin "36") (pinfunction "PL1(ICP5)_36") (pintype "bidirectional"))
      (node (ref "XIOL") (pin "6") (pinfunction "6_6") (pintype "passive"))
    )
    (net (code "65") (name "/D49") (class "Default")
      (node (ref "IC9") (pin "35") (pinfunction "PL0(ICP4)_35") (pintype "bidirectional"))
      (node (ref "XIOL") (pin "5") (pinfunction "5_5") (pintype "passive"))
    )
    (net (code "66") (name "/D50_MISO") (class "Default")
      (node (ref "IC6") (pin "27") (pinfunction "MISO_27") (pintype "bidirectional"))
      (node (ref "IC9") (pin "22") (pinfunction "(MISO/PCINT3)PB3_22") (pintype "bidirectional"))
      (node (ref "ICSP") (pin "1") (pinfunction "1_1") (pintype "passive"))
      (node (ref "P4") (pin "7") (pinfunction "DO_7") (pintype "bidirectional"))
      (node (ref "XIOL") (pin "4") (pinfunction "4_4") (pintype "passive"))
    )
    (net (code "67") (name "/D51_MOSI") (class "Default")
      (node (ref "IC6") (pin "28") (pinfunction "MOSI_28") (pintype "bidirectional"))
      (node (ref "IC9") (pin "21") (pinfunction "(MOSI/PCINT2)PB2_21") (pintype "bidirectional"))
      (node (ref "ICSP") (pin "4") (pinfunction "4_4") (pintype "passive"))
      (node (ref "RN6") (pin "6") (pinfunction "2_6") (pintype "passive"))
      (node (ref "XIOL") (pin "3") (pinfunction "3_3") (pintype "passive"))
    )
    (net (code "68") (name "/D52_SCK") (class "Default")
      (node (ref "IC6") (pin "30") (pinfunction "SCLK_30") (pintype "bidirectional"))
      (node (ref "IC9") (pin "20") (pinfunction "(SCK/PCINT1)PB1_20") (pintype "bidirectional"))
      (node (ref "ICSP") (pin "3") (pinfunction "3_3") (pintype "passive"))
      (node (ref "RN6") (pin "5") (pinfunction "2_5") (pintype "passive"))
      (node (ref "XIOL") (pin "2") (pinfunction "2_2") (pintype "passive"))
    )
    (net (code "69") (name "/D53_SS") (class "Default")
      (node (ref "IC9") (pin "19") (pinfunction "(SS/PCINT0)PB0_19") (pintype "bidirectional"))
      (node (ref "XIOL") (pin "1") (pinfunction "1_1") (pintype "passive"))
    )
    (net (code "70") (name "/DTR") (class "Default")
      (node (ref "IC3") (pin "13") (pinfunction "(CTS)PD7_13") (pintype "bidirectional"))
      (node (ref "JP7") (pin "2") (pinfunction "2_2") (pintype "passive"))
      (node (ref "SJ2") (pin "2") (pinfunction "2_2") (pintype "passive"))
      (node (ref "SJ3") (pin "1") (pinfunction "1_1") (pintype "passive"))
    )
    (net (code "71") (name "/FDXLED") (class "Default")
      (node (ref "IC6") (pin "70") (pinfunction "FDXLED_70") (pintype "bidirectional"))
      (node (ref "RN1") (pin "4") (pinfunction "1_4") (pintype "passive"))
      (node (ref "RN2") (pin "8") (pinfunction "2_8") (pintype "passive"))
    )
    (net (code "72") (name "/LINKLED") (class "Default")
      (node (ref "IC6") (pin "66") (pinfunction "LINKLED_66") (pintype "bidirectional"))
      (node (ref "RN2") (pin "4") (pinfunction "1_4") (pintype "passive"))
      (node (ref "RN2") (pin "7") (pinfunction "2_7") (pintype "passive"))
    )
    (net (code "73") (name "/MISO2") (class "Default")
      (node (ref "IC3") (pin "17") (pinfunction "(MISO)PB3_17") (pintype "bidirectional"))
      (node (ref "P3") (pin "1") (pinfunction "1_1") (pintype "passive"))
    )
    (net (code "74") (name "/MOSI2") (class "Default")
      (node (ref "IC3") (pin "16") (pinfunction "(MOSI)PB2_16") (pintype "bidirectional"))
      (node (ref "P3") (pin "4") (pinfunction "4_4") (pintype "passive"))
    )
    (net (code "75") (name "/NC") (class "Default")
      (node (ref "JP6") (pin "8") (pinfunction "8_8") (pintype "passive"))
    )
    (net (code "76") (name "/RD+") (class "Default")
      (node (ref "IC3") (pin "29") (pinfunction "D+_29") (pintype "bidirectional"))
      (node (ref "R5") (pin "1") (pinfunction "1_1") (pintype "passive"))
    )
    (net (code "77") (name "/RD-") (class "Default")
      (node (ref "IC3") (pin "30") (pinfunction "D-_30") (pintype "bidirectional"))
      (node (ref "R4") (pin "1") (pinfunction "1_1") (pintype "passive"))
    )
    (net (code "78") (name "/RESET") (class "Default")
      (node (ref "C19") (pin "2") (pinfunction "2_2") (pintype "passive"))
      (node (ref "IC2") (pin "3") (pinfunction "/MR_3") (pintype "input"))
      (node (ref "IC9") (pin "30") (pinfunction "RESET_30") (pintype "input"))
      (node (ref "ICSP") (pin "5") (pinfunction "5_5") (pintype "passive"))
      (node (ref "JP6") (pin "6") (pinfunction "6_6") (pintype "passive"))
      (node (ref "RN4") (pin "2") (pinfunction "1_2") (pintype "passive"))
      (node (ref "S1") (pin "3") (pinfunction "3_3") (pintype "passive"))
      (node (ref "S1") (pin "4") (pinfunction "4_4") (pintype "passive"))
    )
    (net (code "79") (name "/RESET2") (class "Default")
      (node (ref "IC3") (pin "24") (pinfunction "RESET_24") (pintype "input"))
      (node (ref "P3") (pin "5") (pinfunction "5_5") (pintype "passive"))
      (node (ref "RN4") (pin "1") (pinfunction "1_1") (pintype "passive"))
    )
    (net (code "80") (name "/RXD1") (class "Default")
      (node (ref "COMMUNICATION1") (pin "3") (pinfunction "3_3") (pintype "passive"))
      (node (ref "IC9") (pin "45") (pinfunction "(RXD1/INT2)PD2_45") (pintype "bidirectional"))
    )
    (net (code "81") (name "/RXD2") (class "Default")
      (node (ref "COMMUNICATION1") (pin "5") (pinfunction "5_5") (pintype "passive"))
      (node (ref "IC9") (pin "12") (pinfunction "PH0(RXD2)_12") (pintype "bidirectional"))
    )
    (net (code "82") (name "/RXD3") (class "Default")
      (node (ref "COMMUNICATION1") (pin "7") (pinfunction "7_7") (pintype "passive"))
      (node (ref "IC9") (pin "63") (pinfunction "PJ0(RXD3/PCINT9)_63") (pintype "bidirectional"))
    )
    (net (code "83") (name "/RXIN") (class "Default")
      (node (ref "IC6") (pin "6") (pinfunction "RXIN_6") (pintype "bidirectional"))
      (node (ref "RN5") (pin "2") (pinfunction "1_2") (pintype "passive"))
      (node (ref "U1") (pin "P$2") (pinfunction "RX-_P$2") (pintype "bidirectional"))
    )
    (net (code "84") (name "/RXIP") (class "Default")
      (node (ref "IC6") (pin "5") (pinfunction "RXIP_5") (pintype "bidirectional"))
      (node (ref "RN5") (pin "1") (pinfunction "1_1") (pintype "passive"))
      (node (ref "U1") (pin "P$1") (pinfunction "RX+_P$1") (pintype "bidirectional"))
    )
    (net (code "85") (name "/RXLED") (class "Default")
      (node (ref "IC3") (pin "10") (pinfunction "PD4_10") (pintype "bidirectional"))
      (node (ref "RN3") (pin "7") (pinfunction "2_7") (pintype "passive"))
    )
    (net (code "86") (name "/SCK2") (class "Default")
      (node (ref "IC3") (pin "15") (pinfunction "(SCLK)PB1_15") (pintype "bidirectional"))
      (node (ref "P3") (pin "3") (pinfunction "3_3") (pintype "passive"))
    )
    (net (code "87") (name "/SCL") (class "Default")
      (node (ref "COMMUNICATION1") (pin "1") (pinfunction "1_1") (pintype "passive"))
      (node (ref "IC9") (pin "43") (pinfunction "(SCL/INT0)PD0_43") (pintype "bidirectional"))
      (node (ref "JP4") (pin "2") (pinfunction "2_2") (pintype "passive"))
      (node (ref "PWMH") (pin "10") (pinfunction "10_10") (pintype "passive"))
      (node (ref "SJ6") (pin "1") (pinfunction "1_1") (pintype "passive"))
    )
    (net (code "88") (name "/SDA") (class "Default")
      (node (ref "COMMUNICATION1") (pin "2") (pinfunction "2_2") (pintype "passive"))
      (node (ref "IC9") (pin "44") (pinfunction "(SDA/INT1)PD1_44") (pintype "bidirectional"))
      (node (ref "JP4") (pin "3") (pinfunction "3_3") (pintype "passive"))
      (node (ref "PWMH") (pin "9") (pinfunction "9_9") (pintype "passive"))
      (node (ref "SJ5") (pin "1") (pinfunction "1_1") (pintype "passive"))
    )
    (net (code "89") (name "/SEN") (class "Default")
      (node (ref "IC6") (pin "31") (pinfunction "SEN_31") (pintype "bidirectional"))
      (node (ref "Q3") (pin "3") (pinfunction "D_3") (pintype "passive"))
      (node (ref "RN7") (pin "4") (pinfunction "1_4") (pintype "passive"))
    )
    (net (code "90") (name "/SPDLED") (class "Default")
      (node (ref "IC6") (pin "67") (pinfunction "SPDLED_67") (pintype "bidirectional"))
      (node (ref "RN2") (pin "3") (pinfunction "1_3") (pintype "passive"))
    )
    (net (code "91") (name "/TXD1") (class "Default")
      (node (ref "COMMUNICATION1") (pin "4") (pinfunction "4_4") (pintype "passive"))
      (node (ref "IC9") (pin "46") (pinfunction "(TXD1/INT3)PD3_46") (pintype "bidirectional"))
    )
    (net (code "92") (name "/TXD2") (class "Default")
      (node (ref "COMMUNICATION1") (pin "6") (pinfunction "6_6") (pintype "passive"))
      (node (ref "IC9") (pin "13") (pinfunction "PH1(TXD2)_13") (pintype "bidirectional"))
    )
    (net (code "93") (name "/TXD3") (class "Default")
      (node (ref "COMMUNICATION1") (pin "8") (pinfunction "8_8") (pintype "passive"))
      (node (ref "IC9") (pin "64") (pinfunction "PJ1(TXD3/PCINT10)_64") (pintype "bidirectional"))
    )
    (net (code "94") (name "/TXLED") (class "Default")
      (node (ref "IC3") (pin "11") (pinfunction "(XCK)PD5_11") (pintype "bidirectional"))
      (node (ref "RN3") (pin "8") (pinfunction "2_8") (pintype "passive"))
    )
    (net (code "95") (name "/TXON") (class "Default")
      (node (ref "IC6") (pin "9") (pinfunction "TXON_9") (pintype "bidirectional"))
      (node (ref "RN5") (pin "4") (pinfunction "1_4") (pintype "passive"))
      (node (ref "U1") (pin "P$6") (pinfunction "TX-_P$6") (pintype "bidirectional"))
    )
    (net (code "96") (name "/TXOP") (class "Default")
      (node (ref "IC6") (pin "8") (pinfunction "TXOP_8") (pintype "bidirectional"))
      (node (ref "RN5") (pin "3") (pinfunction "1_3") (pintype "passive"))
      (node (ref "U1") (pin "P$5") (pinfunction "TX+_P$5") (pintype "bidirectional"))
    )
    (net (code "97") (name "/USBRXD") (class "Default")
      (node (ref "IC3") (pin "9") (pinfunction "(TXD1)PD3_9") (pintype "bidirectional"))
      (node (ref "RN3") (pin "5") (pinfunction "2_5") (pintype "passive"))
    )
    (net (code "98") (name "/USBTXD") (class "Default")
      (node (ref "IC3") (pin "8") (pinfunction "(RXD1)PD2_8") (pintype "bidirectional"))
      (node (ref "RN3") (pin "6") (pinfunction "2_6") (pintype "passive"))
    )
    (net (code "99") (name "/USBVCC") (class "Default")
      (node (ref "F1") (pin "2") (pinfunction "2_2") (pintype "passive"))
      (node (ref "IC3") (pin "31") (pinfunction "UVCC_31") (pintype "power_in"))
      (node (ref "JP5") (pin "1") (pinfunction "1_1") (pintype "passive"))
    )
    (net (code "100") (name "/VIN") (class "Default")
      (node (ref "C36") (pin "1") (pinfunction "1_1") (pintype "passive"))
      (node (ref "D1") (pin "C") (pinfunction "C_C") (pintype "passive"))
      (node (ref "IC1") (pin "2") (pinfunction "IN_2") (pintype "power_in"))
      (node (ref "JP3") (pin "4") (pinfunction "VIN[4]_4") (pintype "passive"))
      (node (ref "JP6") (pin "1") (pinfunction "1_1") (pintype "passive"))
      (node (ref "R10") (pin "1") (pinfunction "1_1") (pintype "passive"))
    )
    (net (code "101") (name "/WIZRST") (class "Default")
      (node (ref "IC2") (pin "2") (pinfunction "/RESET_2") (pintype "output"))
      (node (ref "IC6") (pin "59") (pinfunction "/RESET_59") (pintype "bidirectional"))
    )
    (net (code "102") (name "/WRXLED") (class "Default")
      (node (ref "IC6") (pin "72") (pinfunction "RXLED_72") (pintype "bidirectional"))
      (node (ref "RN1") (pin "2") (pinfunction "1_2") (pintype "passive"))
    )
    (net (code "103") (name "/WTXLED") (class "Default")
      (node (ref "IC6") (pin "73") (pinfunction "TXLED_73") (pintype "bidirectional"))
      (node (ref "RN1") (pin "1") (pinfunction "1_1") (pintype "passive"))
    )
    (net (code "104") (name "/XTAL1") (class "Default")
      (node (ref "C21") (pin "2") (pinfunction "2_2") (pintype "passive"))
      (node (ref "IC9") (pin "34") (pinfunction "XTAL1_34") (pintype "input"))
      (node (ref "R7") (pin "1") (pinfunction "1_1") (pintype "passive"))
      (node (ref "X3") (pin "1") (pinfunction "1_1") (pintype "passive"))
    )
    (net (code "105") (name "/XTAL2") (class "Default")
      (node (ref "C20") (pin "2") (pinfunction "2_2") (pintype "passive"))
      (node (ref "IC9") (pin "33") (pinfunction "XTAL2_33") (pintype "output"))
      (node (ref "R7") (pin "2") (pinfunction "2_2") (pintype "passive"))
      (node (ref "X3") (pin "2") (pinfunction "2_2") (pintype "passive"))
    )
    (net (code "106") (name "5V") (class "Default")
      (node (ref "C12") (pin "1") (pinfunction "1_1") (pintype "passive"))
      (node (ref "C31") (pin "1") (pinfunction "1_1") (pintype "passive"))
      (node (ref "C33") (pin "1") (pinfunction "1_1") (pintype "passive"))
      (node (ref "C34") (pin "1") (pinfunction "1_1") (pintype "passive"))
      (node (ref "C6") (pin "2") (pinfunction "2_2") (pintype "passive"))
      (node (ref "C7") (pin "1") (pinfunction "1_1") (pintype "passive"))
      (node (ref "C9") (pin "1") (pinfunction "1_1") (pintype "passive"))
      (node (ref "IC2") (pin "4") (pinfunction "VCC_4") (pintype "power_in"))
      (node (ref "IC3") (pin "32") (pinfunction "AVCC_32") (pintype "power_in"))
      (node (ref "IC3") (pin "4") (pinfunction "VCC_4") (pintype "power_in"))
      (node (ref "IC4") (pin "6") (pinfunction "VCC_6") (pintype "power_in"))
      (node (ref "IC9") (pin "10") (pinfunction "VCC_10") (pintype "power_in"))
      (node (ref "IC9") (pin "100") (pinfunction "AVCC_100") (pintype "power_in"))
      (node (ref "IC9") (pin "31") (pinfunction "VCC1_31") (pintype "power_in"))
      (node (ref "IC9") (pin "61") (pinfunction "VCC2_61") (pintype "power_in"))
      (node (ref "IC9") (pin "80") (pinfunction "VCC3_80") (pintype "power_in"))
      (node (ref "ICSP") (pin "2") (pinfunction "2_2") (pintype "passive"))
      (node (ref "JP1") (pin "1") (pinfunction "1_1") (pintype "passive"))
      (node (ref "JP1") (pin "2") (pinfunction "2_2") (pintype "passive"))
      (node (ref "JP4") (pin "1") (pinfunction "1_1") (pintype "passive"))
      (node (ref "JP5") (pin "2") (pinfunction "2_2") (pintype "passive"))
      (node (ref "JP6") (pin "4") (pinfunction "4_4") (pintype "passive"))
      (node (ref "JP6") (pin "7") (pinfunction "7_7") (pintype "passive"))
      (node (ref "LED10") (pin "A") (pinfunction "A_A") (pintype "passive"))
      (node (ref "LED2") (pin "A") (pinfunction "A_A") (pintype "passive"))
      (node (ref "LED5") (pin "A") (pinfunction "A_A") (pintype "passive"))
      (node (ref "LED6") (pin "A") (pinfunction "A_A") (pintype "passive"))
      (node (ref "P3") (pin "2") (pinfunction "2_2") (pintype "passive"))
      (node (ref "R14") (pin "1") (pinfunction "1_1") (pintype "passive"))
      (node (ref "R15") (pin "1") (pinfunction "1_1") (pintype "passive"))
      (node (ref "REG1") (pin "3") (pinfunction "IN_3") (pintype "input"))
      (node (ref "REG2") (pin "3") (pinfunction "IN_3") (pintype "input"))
      (node (ref "RN4") (pin "7") (pinfunction "2_7") (pintype "passive"))
      (node (ref "RN4") (pin "8") (pinfunction "2_8") (pintype "passive"))
    )
    (net (code "107") (name "GND") (class "Default")
      (node (ref "C1") (pin "2") (pinfunction "2_2") (pintype "passive"))
      (node (ref "C10") (pin "C") (pinfunction "-_C") (pintype "passive"))
      (node (ref "C11") (pin "2") (pinfunction "2_2") (pintype "passive"))
      (node (ref "C12") (pin "2") (pinfunction "2_2") (pintype "passive"))
      (node (ref "C13") (pin "C") (pinfunction "-_C") (pintype "passive"))
      (node (ref "C15") (pin "2") (pinfunction "2_2") (pintype "passive"))
      (node (ref "C16") (pin "2") (pinfunction "2_2") (pintype "passive"))
      (node (ref "C17") (pin "2") (pinfunction "2_2") (pintype "passive"))
      (node (ref "C18") (pin "2") (pinfunction "2_2") (pintype "passive"))
      (node (ref "C2") (pin "1") (pinfunction "1_1") (pintype "passive"))
      (node (ref "C20") (pin "1") (pinfunction "1_1") (pintype "passive"))
      (node (ref "C21") (pin "1") (pinfunction "1_1") (pintype "passive"))
      (node (ref "C22") (pin "2") (pinfunction "2_2") (pintype "passive"))
      (node (ref "C23") (pin "2") (pinfunction "2_2") (pintype "passive"))
      (node (ref "C24") (pin "2") (pinfunction "2_2") (pintype "passive"))
      (node (ref "C25") (pin "2") (pinfunction "2_2") (pintype "passive"))
      (node (ref "C26") (pin "2") (pinfunction "2_2") (pintype "passive"))
      (node (ref "C27") (pin "2") (pinfunction "2_2") (pintype "passive"))
      (node (ref "C28") (pin "2") (pinfunction "2_2") (pintype "passive"))
      (node (ref "C29") (pin "2") (pinfunction "2_2") (pintype "passive"))
      (node (ref "C3") (pin "C") (pinfunction "-_C") (pintype "passive"))
      (node (ref "C30") (pin "2") (pinfunction "2_2") (pintype "passive"))
      (node (ref "C31") (pin "2") (pinfunction "2_2") (pintype "passive"))
      (node (ref "C33") (pin "2") (pinfunction "2_2") (pintype "passive"))
      (node (ref "C34") (pin "2") (pinfunction "2_2") (pintype "passive"))
      (node (ref "C35") (pin "2") (pinfunction "2_2") (pintype "passive"))
      (node (ref "C36") (pin "2") (pinfunction "2_2") (pintype "passive"))
      (node (ref "C37") (pin "2") (pinfunction "2_2") (pintype "passive"))
      (node (ref "C4") (pin "C") (pinfunction "-_C") (pintype "passive"))
      (node (ref "C6") (pin "1") (pinfunction "1_1") (pintype "passive"))
      (node (ref "C7") (pin "2") (pinfunction "2_2") (pintype "passive"))
      (node (ref "C8") (pin "1") (pinfunction "1_1") (pintype "passive"))
      (node (ref "C9") (pin "2") (pinfunction "2_2") (pintype "passive"))
      (node (ref "IC1") (pin "4") (pinfunction "GND_4") (pintype "power_in"))
      (node (ref "IC1") (pin "9") (pinfunction "TGND_9") (pintype "power_in"))
      (node (ref "IC2") (pin "1") (pinfunction "GND_1") (pintype "power_in"))
      (node (ref "IC3") (pin "3") (pinfunction "GND_3") (pintype "power_in"))
      (node (ref "IC3") (pin "EXP") (pinfunction "PAD_EXP") (pintype "power_in"))
      (node (ref "IC4") (pin "2") (pinfunction "GND_2") (pintype "power_in"))
      (node (ref "IC4") (pin "4") (pinfunction "A1_4") (pintype "input"))
      (node (ref "IC4") (pin "5") (pinfunction "A0_5") (pintype "input"))
      (node (ref "IC6") (pin "10") (pinfunction "GNDA1_10") (pintype "bidirectional"))
      (node (ref "IC6") (pin "13") (pinfunction "GNDD0_13") (pintype "bidirectional"))
      (node (ref "IC6") (pin "14") (pinfunction "GNDD1_14") (pintype "bidirectional"))
      (node (ref "IC6") (pin "17") (pinfunction "GNDD2_17") (pintype "bidirectional"))
      (node (ref "IC6") (pin "19") (pinfunction "DATA7_19") (pintype "bidirectional"))
      (node (ref "IC6") (pin "20") (pinfunction "DATA6_20") (pintype "bidirectional"))
      (node (ref "IC6") (pin "21") (pinfunction "DATA5_21") (pintype "bidirectional"))
      (node (ref "IC6") (pin "22") (pinfunction "DATA4_22") (pintype "bidirectional"))
      (node (ref "IC6") (pin "23") (pinfunction "DATA3_23") (pintype "bidirectional"))
      (node (ref "IC6") (pin "24") (pinfunction "DATA2_24") (pintype "bidirectional"))
      (node (ref "IC6") (pin "25") (pinfunction "DATA1_25") (pintype "bidirectional"))
      (node (ref "IC6") (pin "26") (pinfunction "DATA0_26") (pintype "bidirectional"))
      (node (ref "IC6") (pin "32") (pinfunction "GNDD3_32") (pintype "bidirectional"))
      (node (ref "IC6") (pin "34") (pinfunction "TEST_MODE3_34") (pintype "bidirectional"))
      (node (ref "IC6") (pin "35") (pinfunction "TEST_MODE2_35") (pintype "bidirectional"))
      (node (ref "IC6") (pin "36") (pinfunction "TEST_MODE1_36") (pintype "bidirectional"))
      (node (ref "IC6") (pin "37") (pinfunction "TEST_MODE0_37") (pintype "bidirectional"))
      (node (ref "IC6") (pin "38") (pinfunction "ADDR14_38") (pintype "bidirectional"))
      (node (ref "IC6") (pin "39") (pinfunction "ADDR13_39") (pintype "bidirectional"))
      (node (ref "IC6") (pin "4") (pinfunction "GNDA0_4") (pintype "bidirectional"))
      (node (ref "IC6") (pin "40") (pinfunction "ADDR12_40") (pintype "bidirectional"))
      (node (ref "IC6") (pin "41") (pinfunction "ADDR11_41") (pintype "bidirectional"))
      (node (ref "IC6") (pin "42") (pinfunction "ADDR10_42") (pintype "bidirectional"))
      (node (ref "IC6") (pin "43") (pinfunction "GNDD4_43") (pintype "bidirectional"))
      (node (ref "IC6") (pin "45") (pinfunction "ADDR9_45") (pintype "bidirectional"))
      (node (ref "IC6") (pin "46") (pinfunction "ADDR8_46") (pintype "bidirectional"))
      (node (ref "IC6") (pin "47") (pinfunction "ADDR7_47") (pintype "bidirectional"))
      (node (ref "IC6") (pin "48") (pinfunction "ADDR6_48") (pintype "bidirectional"))
      (node (ref "IC6") (pin "49") (pinfunction "ADDR5_49") (pintype "bidirectional"))
      (node (ref "IC6") (pin "50") (pinfunction "ADDR4_50") (pintype "bidirectional"))
      (node (ref "IC6") (pin "51") (pinfunction "ADDR3_51") (pintype "bidirectional"))
      (node (ref "IC6") (pin "52") (pinfunction "ADDR2_52") (pintype "bidirectional"))
      (node (ref "IC6") (pin "53") (pinfunction "ADDR1_53") (pintype "bidirectional"))
      (node (ref "IC6") (pin "54") (pinfunction "ADDR0_54") (pintype "bidirectional"))
      (node (ref "IC6") (pin "63") (pinfunction "OPMODE0_63") (pintype "bidirectional"))
      (node (ref "IC6") (pin "64") (pinfunction "OPMODE1_64") (pintype "bidirectional"))
      (node (ref "IC6") (pin "65") (pinfunction "OPMODE2_65") (pintype "bidirectional"))
      (node (ref "IC6") (pin "68") (pinfunction "GNDD5_68") (pintype "bidirectional"))
      (node (ref "IC6") (pin "77") (pinfunction "GNDA2_77") (pintype "bidirectional"))
      (node (ref "IC9") (pin "11") (pinfunction "GND_11") (pintype "power_in"))
      (node (ref "IC9") (pin "32") (pinfunction "GND1_32") (pintype "power_in"))
      (node (ref "IC9") (pin "62") (pinfunction "GND2_62") (pintype "power_in"))
      (node (ref "IC9") (pin "81") (pinfunction "GND3_81") (pintype "power_in"))
      (node (ref "IC9") (pin "99") (pinfunction "AGND_99") (pintype "power_in"))
      (node (ref "ICSP") (pin "6") (pinfunction "6_6") (pintype "passive"))
      (node (ref "J1") (pin "GND") (pinfunction "GND_GND") (pintype "bidirectional"))
      (node (ref "J1") (pin "GNDBREAK") (pinfunction "GNDBREAK_GNDBREAK") (pintype "bidirectional"))
      (node (ref "JP2") (pin "1") (pinfunction "1_1") (pintype "passive"))
      (node (ref "JP2") (pin "2") (pinfunction "2_2") (pintype "passive"))
      (node (ref "JP3") (pin "1") (pinfunction "GND[1]_1") (pintype "passive"))
      (node (ref "JP3") (pin "MNT1") (pinfunction "MNT1_MNT1") (pintype "passive"))
      (node (ref "JP3") (pin "MNT2") (pinfunction "MNT2_MNT2") (pintype "passive"))
      (node (ref "JP4") (pin "4") (pinfunction "4_4") (pintype "passive"))
      (node (ref "JP6") (pin "2") (pinfunction "2_2") (pintype "passive"))
      (node (ref "JP6") (pin "3") (pinfunction "3_3") (pintype "passive"))
      (node (ref "P3") (pin "6") (pinfunction "6_6") (pintype "passive"))
      (node (ref "P4") (pin "6") (pinfunction "GND_6") (pintype "bidirectional"))
      (node (ref "P4") (pin "GND1") (pinfunction "SHIELD1_GND1") (pintype "bidirectional"))
      (node (ref "P4") (pin "GND2") (pinfunction "SHIELD2_GND2") (pintype "bidirectional"))
      (node (ref "P4") (pin "GND3") (pinfunction "CD1_GND3") (pintype "bidirectional"))
      (node (ref "P4") (pin "GND4") (pinfunction "CD2_GND4") (pintype "bidirectional"))
      (node (ref "PWMH") (pin "7") (pinfunction "7_7") (pintype "passive"))
      (node (ref "Q2") (pin "2") (pinfunction "S_2") (pintype "passive"))
      (node (ref "Q3") (pin "2") (pinfunction "S_2") (pintype "passive"))
      (node (ref "R11") (pin "1") (pinfunction "1_1") (pintype "passive"))
      (node (ref "R13") (pin "1") (pinfunction "1_1") (pintype "passive"))
      (node (ref "R6") (pin "1") (pinfunction "1_1") (pintype "passive"))
      (node (ref "REG1") (pin "1") (pinfunction "ADJ_1") (pintype "input"))
      (node (ref "REG2") (pin "1") (pinfunction "ADJ_1") (pintype "input"))
      (node (ref "RN8") (pin "1") (pinfunction "1_1") (pintype "passive"))
      (node (ref "RN8") (pin "2") (pinfunction "1_2") (pintype "passive"))
      (node (ref "RN8") (pin "3") (pinfunction "1_3") (pintype "passive"))
      (node (ref "S1") (pin "1") (pinfunction "1_1") (pintype "passive"))
      (node (ref "S1") (pin "2") (pinfunction "2_2") (pintype "passive"))
      (node (ref "SJ1") (pin "2") (pinfunction "2_2") (pintype "passive"))
      (node (ref "SJ2") (pin "1") (pinfunction "1_1") (pintype "passive"))
      (node (ref "U1") (pin "GND1") (pinfunction "GND1_GND1") (pintype "bidirectional"))
      (node (ref "U1") (pin "GND2") (pinfunction "GND2_GND2") (pintype "bidirectional"))
    )
    (net (code "108") (name "Net-(C1-Pad1)") (class "Default")
      (node (ref "C1") (pin "1") (pinfunction "1_1") (pintype "passive"))
      (node (ref "R9") (pin "1") (pinfunction "1_1") (pintype "passive"))
    )
    (net (code "109") (name "Net-(C8-Pad2)") (class "Default")
      (node (ref "C8") (pin "2") (pinfunction "2_2") (pintype "passive"))
      (node (ref "R1") (pin "1") (pinfunction "1_1") (pintype "passive"))
      (node (ref "R2") (pin "2") (pinfunction "2_2") (pintype "passive"))
      (node (ref "X1") (pin "1") (pinfunction "1_1") (pintype "passive"))
    )
    (net (code "110") (name "Net-(C19-Pad1)") (class "Default")
      (node (ref "C19") (pin "1") (pinfunction "1_1") (pintype "passive"))
      (node (ref "JP7") (pin "1") (pinfunction "1_1") (pintype "passive"))
      (node (ref "SJ3") (pin "2") (pinfunction "2_2") (pintype "passive"))
    )
    (net (code "111") (name "Net-(D1-PadA)") (class "Default")
      (node (ref "D1") (pin "A") (pinfunction "A_A") (pintype "passive"))
      (node (ref "J1") (pin "PWR") (pinfunction "PWR_PWR") (pintype "bidirectional"))
    )
    (net (code "112") (name "Net-(F1-Pad1)") (class "Default")
      (node (ref "F1") (pin "1") (pinfunction "1_1") (pintype "passive"))
      (node (ref "P1") (pin "VBUS") (pinfunction "VBUS_VBUS") (pintype "bidirectional"))
    )
    (net (code "113") (name "Net-(IC1-BS)") (class "Default")
      (node (ref "C32") (pin "2") (pinfunction "2_2") (pintype "passive"))
      (node (ref "IC1") (pin "1") (pinfunction "BS_1") (pintype "bidirectional"))
    )
    (net (code "114") (name "Net-(IC1-COMP)") (class "Default")
      (node (ref "C35") (pin "1") (pinfunction "1_1") (pintype "passive"))
      (node (ref "IC1") (pin "6") (pinfunction "COMP_6") (pintype "bidirectional"))
      (node (ref "R9") (pin "2") (pinfunction "2_2") (pintype "passive"))
    )
    (net (code "115") (name "Net-(IC1-EN)") (class "Default")
      (node (ref "IC1") (pin "7") (pinfunction "EN_7") (pintype "input"))
      (node (ref "R10") (pin "2") (pinfunction "2_2") (pintype "passive"))
    )
    (net (code "116") (name "Net-(IC1-FB)") (class "Default")
      (node (ref "IC1") (pin "5") (pinfunction "FB_5") (pintype "bidirectional"))
      (node (ref "R11") (pin "2") (pinfunction "2_2") (pintype "passive"))
      (node (ref "R12") (pin "1") (pinfunction "1_1") (pintype "passive"))
    )
    (net (code "117") (name "Net-(IC1-SS)") (class "Default")
      (node (ref "C27") (pin "1") (pinfunction "1_1") (pintype "passive"))
      (node (ref "IC1") (pin "8") (pinfunction "SS_8") (pintype "bidirectional"))
    )
    (net (code "118") (name "Net-(IC1-SW)") (class "Default")
      (node (ref "C32") (pin "1") (pinfunction "1_1") (pintype "passive"))
      (node (ref "IC1") (pin "3") (pinfunction "SW_3") (pintype "bidirectional"))
      (node (ref "L4") (pin "1") (pinfunction "1_1") (pintype "bidirectional"))
    )
    (net (code "119") (name "Net-(IC3-UCAP)") (class "Default")
      (node (ref "C11") (pin "1") (pinfunction "1_1") (pintype "passive"))
      (node (ref "IC3") (pin "27") (pinfunction "UCAP_27") (pintype "passive"))
    )
    (net (code "120") (name "Net-(IC3-UGND)") (class "Default")
      (node (ref "IC3") (pin "28") (pinfunction "UGND_28") (pintype "power_in"))
      (node (ref "L3") (pin "2") (pinfunction "2_2") (pintype "passive"))
      (node (ref "P1") (pin "GND") (pinfunction "GND_GND") (pintype "bidirectional"))
      (node (ref "SJ1") (pin "1") (pinfunction "1_1") (pintype "passive"))
    )
    (net (code "121") (name "Net-(IC3-XTAL1)") (class "Default")
      (node (ref "IC3") (pin "1") (pinfunction "XTAL1_1") (pintype "bidirectional"))
      (node (ref "R2") (pin "1") (pinfunction "1_1") (pintype "passive"))
    )
    (net (code "122") (name "Net-(IC3-XTAL2)") (class "Default")
      (node (ref "C2") (pin "2") (pinfunction "2_2") (pintype "passive"))
      (node (ref "IC3") (pin "2") (pinfunction "XTAL2_2") (pintype "bidirectional"))
      (node (ref "R1") (pin "2") (pinfunction "2_2") (pintype "passive"))
      (node (ref "X1") (pin "2") (pinfunction "2_2") (pintype "passive"))
    )
    (net (code "123") (name "Net-(IC4-SCL)") (class "Default")
      (node (ref "IC4") (pin "1") (pinfunction "SCL_1") (pintype "bidirectional"))
      (node (ref "R15") (pin "2") (pinfunction "2_2") (pintype "passive"))
      (node (ref "SJ6") (pin "2") (pinfunction "2_2") (pintype "passive"))
    )
    (net (code "124") (name "Net-(IC4-SDA)") (class "Default")
      (node (ref "IC4") (pin "3") (pinfunction "SDA_3") (pintype "bidirectional"))
      (node (ref "R14") (pin "2") (pinfunction "2_2") (pintype "passive"))
      (node (ref "SJ5") (pin "2") (pinfunction "2_2") (pintype "passive"))
    )
    (net (code "125") (name "Net-(IC6-RSET_BG)") (class "Default")
      (node (ref "IC6") (pin "1") (pinfunction "RSET_BG_1") (pintype "bidirectional"))
      (node (ref "R6") (pin "2") (pinfunction "2_2") (pintype "passive"))
    )
    (net (code "126") (name "Net-(IC6-XTLN)") (class "Default")
      (node (ref "C16") (pin "1") (pinfunction "1_1") (pintype "passive"))
      (node (ref "IC6") (pin "75") (pinfunction "XTLN_75") (pintype "bidirectional"))
      (node (ref "R3") (pin "2") (pinfunction "2_2") (pintype "passive"))
      (node (ref "X2") (pin "2") (pinfunction "2_2") (pintype "passive"))
    )
    (net (code "127") (name "Net-(IC6-XTLP)") (class "Default")
      (node (ref "C15") (pin "1") (pinfunction "1_1") (pintype "passive"))
      (node (ref "IC6") (pin "76") (pinfunction "XTLP_76") (pintype "bidirectional"))
      (node (ref "R3") (pin "1") (pinfunction "1_1") (pintype "passive"))
      (node (ref "X2") (pin "1") (pinfunction "1_1") (pintype "passive"))
    )
    (net (code "128") (name "Net-(IC6-{slash}CS)") (class "Default")
      (node (ref "IC6") (pin "55") (pinfunction "/CS_55") (pintype "bidirectional"))
      (node (ref "IC6") (pin "57") (pinfunction "/WR_57") (pintype "bidirectional"))
      (node (ref "IC6") (pin "58") (pinfunction "/RD_58") (pintype "bidirectional"))
      (node (ref "RN7") (pin "2") (pinfunction "1_2") (pintype "passive"))
    )
    (net (code "129") (name "Net-(IC6-{slash}INT)") (class "Default")
      (node (ref "IC6") (pin "56") (pinfunction "/INT_56") (pintype "bidirectional"))
      (node (ref "SJ4") (pin "2") (pinfunction "2_2") (pintype "passive"))
    )
    (net (code "130") (name "Net-(JP3-V+[3])") (class "Default")
      (node (ref "JP3") (pin "3") (pinfunction "V+[3]_3") (pintype "passive"))
      (node (ref "U1") (pin "P$9") (pinfunction "V+_P$9") (pintype "bidirectional"))
    )
    (net (code "131") (name "Net-(JP3-V-[2])") (class "Default")
      (node (ref "JP3") (pin "2") (pinfunction "V-[2]_2") (pintype "passive"))
      (node (ref "U1") (pin "P$10") (pinfunction "V-_P$10") (pintype "bidirectional"))
    )
    (net (code "132") (name "Net-(L3-Pad1)") (class "Default")
      (node (ref "L3") (pin "1") (pinfunction "1_1") (pintype "passive"))
      (node (ref "P1") (pin "FIX1") (pinfunction "FIX1_FIX1") (pintype "bidirectional"))
      (node (ref "P1") (pin "FIX2") (pinfunction "FIX2_FIX2") (pintype "bidirectional"))
      (node (ref "P1") (pin "PIN1") (pinfunction "PIN1_PIN1") (pintype "bidirectional"))
      (node (ref "P1") (pin "PIN2") (pinfunction "PIN2_PIN2") (pintype "bidirectional"))
      (node (ref "P1") (pin "TAB1") (pinfunction "TAB1_TAB1") (pintype "bidirectional"))
      (node (ref "P1") (pin "TAB2") (pinfunction "TAB2_TAB2") (pintype "bidirectional"))
      (node (ref "Z1") (pin "2") (pinfunction "2_2") (pintype "passive"))
      (node (ref "Z2") (pin "2") (pinfunction "2_2") (pintype "passive"))
    )
    (net (code "133") (name "Net-(LED2-PadC)") (class "Default")
      (node (ref "LED2") (pin "C") (pinfunction "C_C") (pintype "passive"))
      (node (ref "R13") (pin "2") (pinfunction "2_2") (pintype "passive"))
    )
    (net (code "134") (name "Net-(LED5-PadC)") (class "Default")
      (node (ref "LED5") (pin "C") (pinfunction "C_C") (pintype "passive"))
      (node (ref "RN3") (pin "1") (pinfunction "1_1") (pintype "passive"))
    )
    (net (code "135") (name "Net-(LED10-PadC)") (class "Default")
      (node (ref "LED10") (pin "C") (pinfunction "C_C") (pintype "passive"))
      (node (ref "R8") (pin "2") (pinfunction "2_2") (pintype "passive"))
    )
    (net (code "136") (name "Net-(P1-PadD+)") (class "Default")
      (node (ref "P1") (pin "D+") (pinfunction "D+_D+") (pintype "bidirectional"))
      (node (ref "R5") (pin "2") (pinfunction "2_2") (pintype "passive"))
      (node (ref "Z1") (pin "1") (pinfunction "1_1") (pintype "passive"))
    )
    (net (code "137") (name "Net-(P1-PadD-)") (class "Default")
      (node (ref "P1") (pin "D-") (pinfunction "D-_D-") (pintype "bidirectional"))
      (node (ref "R4") (pin "2") (pinfunction "2_2") (pintype "passive"))
      (node (ref "Z2") (pin "1") (pinfunction "1_1") (pintype "passive"))
    )
    (net (code "138") (name "Net-(P4-CS)") (class "Default")
      (node (ref "P4") (pin "2") (pinfunction "CS_2") (pintype "bidirectional"))
      (node (ref "RN6") (pin "2") (pinfunction "1_2") (pintype "passive"))
      (node (ref "RN8") (pin "8") (pinfunction "2_8") (pintype "passive"))
    )
    (net (code "139") (name "Net-(P4-DI)") (class "Default")
      (node (ref "P4") (pin "3") (pinfunction "DI_3") (pintype "bidirectional"))
      (node (ref "RN6") (pin "3") (pinfunction "1_3") (pintype "passive"))
      (node (ref "RN8") (pin "7") (pinfunction "2_7") (pintype "passive"))
    )
    (net (code "140") (name "Net-(P4-SCK)") (class "Default")
      (node (ref "P4") (pin "5") (pinfunction "SCK_5") (pintype "bidirectional"))
      (node (ref "RN6") (pin "4") (pinfunction "1_4") (pintype "passive"))
      (node (ref "RN8") (pin "6") (pinfunction "2_6") (pintype "passive"))
    )
    (net (code "141") (name "Net-(Q2-D)") (class "Default")
      (node (ref "Q2") (pin "3") (pinfunction "D_3") (pintype "passive"))
      (node (ref "R8") (pin "1") (pinfunction "1_1") (pintype "passive"))
    )
    (net (code "142") (name "Net-(RN1A-2)") (class "Default")
      (node (ref "LED1") (pin "C") (pinfunction "C_C") (pintype "passive"))
      (node (ref "RN1") (pin "8") (pinfunction "2_8") (pintype "passive"))
    )
    (net (code "143") (name "Net-(RN1B-2)") (class "Default")
      (node (ref "LED3") (pin "C") (pinfunction "C_C") (pintype "passive"))
      (node (ref "RN1") (pin "7") (pinfunction "2_7") (pintype "passive"))
    )
    (net (code "144") (name "Net-(RN1C-2)") (class "Default")
      (node (ref "LED4") (pin "C") (pinfunction "C_C") (pintype "passive"))
      (node (ref "RN1") (pin "6") (pinfunction "2_6") (pintype "passive"))
    )
    (net (code "145") (name "Net-(RN1D-2)") (class "Default")
      (node (ref "LED7") (pin "C") (pinfunction "C_C") (pintype "passive"))
      (node (ref "RN1") (pin "5") (pinfunction "2_5") (pintype "passive"))
    )
    (net (code "146") (name "Net-(RN2B-1)") (class "Default")
      (node (ref "RN2") (pin "2") (pinfunction "1_2") (pintype "passive"))
      (node (ref "U1") (pin "P$12") (pinfunction "Y-_P$12") (pintype "bidirectional"))
    )
    (net (code "147") (name "Net-(RN2C-2)") (class "Default")
      (node (ref "LED8") (pin "C") (pinfunction "C_C") (pintype "passive"))
      (node (ref "RN2") (pin "6") (pinfunction "2_6") (pintype "passive"))
    )
    (net (code "148") (name "Net-(RN2D-2)") (class "Default")
      (node (ref "LED9") (pin "C") (pinfunction "C_C") (pintype "passive"))
      (node (ref "RN2") (pin "5") (pinfunction "2_5") (pintype "passive"))
    )
    (net (code "149") (name "Net-(RN3B-1)") (class "Default")
      (node (ref "LED6") (pin "C") (pinfunction "C_C") (pintype "passive"))
      (node (ref "RN3") (pin "2") (pinfunction "1_2") (pintype "passive"))
    )
    (net (code "150") (name "Net-(RN5A-2)") (class "Default")
      (node (ref "C23") (pin "1") (pinfunction "1_1") (pintype "passive"))
      (node (ref "RN5") (pin "7") (pinfunction "2_7") (pintype "passive"))
      (node (ref "RN5") (pin "8") (pinfunction "2_8") (pintype "passive"))
    )
    (net (code "151") (name "Net-(RN5C-2)") (class "Default")
      (node (ref "C24") (pin "1") (pinfunction "1_1") (pintype "passive"))
      (node (ref "RN5") (pin "5") (pinfunction "2_5") (pintype "passive"))
      (node (ref "RN5") (pin "6") (pinfunction "2_6") (pintype "passive"))
    )
    (net (code "152") (name "Net-(U1-G-)") (class "Default")
      (node (ref "RN2") (pin "1") (pinfunction "1_1") (pintype "passive"))
      (node (ref "U1") (pin "P$14") (pinfunction "G-_P$14") (pintype "bidirectional"))
    )
    (net (code "153") (name "unconnected-(IC3-(RTS)PD6-Pad12)") (class "Default")
      (node (ref "IC3") (pin "12") (pinfunction "(RTS)PD6_12") (pintype "bidirectional"))
    )
    (net (code "154") (name "unconnected-(IC3-(SS)PB0-Pad14)") (class "Default")
      (node (ref "IC3") (pin "14") (pinfunction "(SS)PB0_14") (pintype "bidirectional"))
    )
    (net (code "155") (name "unconnected-(IC3-PB4-Pad18)") (class "Default")
      (node (ref "IC3") (pin "18") (pinfunction "PB4_18") (pintype "bidirectional"))
    )
    (net (code "156") (name "unconnected-(IC3-PB5-Pad19)") (class "Default")
      (node (ref "IC3") (pin "19") (pinfunction "PB5_19") (pintype "bidirectional"))
    )
    (net (code "157") (name "unconnected-(IC3-PB6-Pad20)") (class "Default")
      (node (ref "IC3") (pin "20") (pinfunction "PB6_20") (pintype "bidirectional"))
    )
    (net (code "158") (name "unconnected-(IC3-PB7-Pad21)") (class "Default")
      (node (ref "IC3") (pin "21") (pinfunction "PB7_21") (pintype "bidirectional"))
    )
    (net (code "159") (name "unconnected-(IC3-PC2-Pad5)") (class "Default")
      (node (ref "IC3") (pin "5") (pinfunction "PC2_5") (pintype "bidirectional"))
    )
    (net (code "160") (name "unconnected-(IC3-PC4-Pad26)") (class "Default")
      (node (ref "IC3") (pin "26") (pinfunction "PC4_26") (pintype "bidirectional"))
    )
    (net (code "161") (name "unconnected-(IC3-PC5-Pad25)") (class "Default")
      (node (ref "IC3") (pin "25") (pinfunction "PC5_25") (pintype "bidirectional"))
    )
    (net (code "162") (name "unconnected-(IC3-PC6-Pad23)") (class "Default")
      (node (ref "IC3") (pin "23") (pinfunction "PC6_23") (pintype "bidirectional"))
    )
    (net (code "163") (name "unconnected-(IC3-PC7-Pad22)") (class "Default")
      (node (ref "IC3") (pin "22") (pinfunction "PC7_22") (pintype "bidirectional"))
    )
    (net (code "164") (name "unconnected-(IC3-PD0-Pad6)") (class "Default")
      (node (ref "IC3") (pin "6") (pinfunction "PD0_6") (pintype "bidirectional"))
    )
    (net (code "165") (name "unconnected-(IC3-PD1-Pad7)") (class "Default")
      (node (ref "IC3") (pin "7") (pinfunction "PD1_7") (pintype "bidirectional"))
    )
    (net (code "166") (name "unconnected-(IC6-NC0-Pad3)") (class "Default")
      (node (ref "IC6") (pin "3") (pinfunction "NC0_3") (pintype "bidirectional"))
    )
    (net (code "167") (name "unconnected-(IC6-NC1-Pad60)") (class "Default")
      (node (ref "IC6") (pin "60") (pinfunction "NC1_60") (pintype "bidirectional"))
    )
    (net (code "168") (name "unconnected-(IC6-NC2-Pad61)") (class "Default")
      (node (ref "IC6") (pin "61") (pinfunction "NC2_61") (pintype "bidirectional"))
    )
    (net (code "169") (name "unconnected-(IC6-NC3-Pad62)") (class "Default")
      (node (ref "IC6") (pin "62") (pinfunction "NC3_62") (pintype "bidirectional"))
    )
    (net (code "170") (name "unconnected-(IC6-NC4-Pad78)") (class "Default")
      (node (ref "IC6") (pin "78") (pinfunction "NC4_78") (pintype "bidirectional"))
    )
    (net (code "171") (name "unconnected-(IC6-NC5-Pad79)") (class "Default")
      (node (ref "IC6") (pin "79") (pinfunction "NC5_79") (pintype "bidirectional"))
    )
    (net (code "172") (name "unconnected-(IC6-NC6-Pad80)") (class "Default")
      (node (ref "IC6") (pin "80") (pinfunction "NC6_80") (pintype "bidirectional"))
    )
    (net (code "173") (name "unconnected-(IC9-(CLKO{slash}ICP3{slash}INT7)PE7-Pad9)") (class "Default")
      (node (ref "IC9") (pin "9") (pinfunction "(CLKO/ICP3/INT7)PE7_9") (pintype "bidirectional"))
    )
    (net (code "174") (name "unconnected-(IC9-(ICP1)PD4-Pad47)") (class "Default")
      (node (ref "IC9") (pin "47") (pinfunction "(ICP1)PD4_47") (pintype "bidirectional"))
    )
    (net (code "175") (name "unconnected-(IC9-(T1)PD6-Pad49)") (class "Default")
      (node (ref "IC9") (pin "49") (pinfunction "(T1)PD6_49") (pintype "bidirectional"))
    )
    (net (code "176") (name "unconnected-(IC9-(T3{slash}INT6)PE6-Pad8)") (class "Default")
      (node (ref "IC9") (pin "8") (pinfunction "(T3/INT6)PE6_8") (pintype "bidirectional"))
    )
    (net (code "177") (name "unconnected-(IC9-(TOSC1)PG4-Pad29)") (class "Default")
      (node (ref "IC9") (pin "29") (pinfunction "(TOSC1)PG4_29") (pintype "bidirectional"))
    )
    (net (code "178") (name "unconnected-(IC9-(TOSC2)PG3-Pad28)") (class "Default")
      (node (ref "IC9") (pin "28") (pinfunction "(TOSC2)PG3_28") (pintype "bidirectional"))
    )
    (net (code "179") (name "unconnected-(IC9-(XCK0{slash}AIN0)PE2-Pad4)") (class "Default")
      (node (ref "IC9") (pin "4") (pinfunction "(XCK0/AIN0)PE2_4") (pintype "bidirectional"))
    )
    (net (code "180") (name "unconnected-(IC9-(XCK1)PD5-Pad48)") (class "Default")
      (node (ref "IC9") (pin "48") (pinfunction "(XCK1)PD5_48") (pintype "bidirectional"))
    )
    (net (code "181") (name "unconnected-(IC9-PH2(XCK2)-Pad14)") (class "Default")
      (node (ref "IC9") (pin "14") (pinfunction "PH2(XCK2)_14") (pintype "bidirectional"))
    )
    (net (code "182") (name "unconnected-(IC9-PH7(T4)-Pad27)") (class "Default")
      (node (ref "IC9") (pin "27") (pinfunction "PH7(T4)_27") (pintype "bidirectional"))
    )
    (net (code "183") (name "unconnected-(IC9-PJ2(XCK3{slash}PCINT11)-Pad65)") (class "Default")
      (node (ref "IC9") (pin "65") (pinfunction "PJ2(XCK3/PCINT11)_65") (pintype "bidirectional"))
    )
    (net (code "184") (name "unconnected-(IC9-PJ3(PCINT12)-Pad66)") (class "Default")
      (node (ref "IC9") (pin "66") (pinfunction "PJ3(PCINT12)_66") (pintype "bidirectional"))
    )
    (net (code "185") (name "unconnected-(IC9-PJ4(PCINT13)-Pad67)") (class "Default")
      (node (ref "IC9") (pin "67") (pinfunction "PJ4(PCINT13)_67") (pintype "bidirectional"))
    )
    (net (code "186") (name "unconnected-(IC9-PJ5(PCINT14)-Pad68)") (class "Default")
      (node (ref "IC9") (pin "68") (pinfunction "PJ5(PCINT14)_68") (pintype "bidirectional"))
    )
    (net (code "187") (name "unconnected-(IC9-PJ6(PCINT15)-Pad69)") (class "Default")
      (node (ref "IC9") (pin "69") (pinfunction "PJ6(PCINT15)_69") (pintype "bidirectional"))
    )
    (net (code "188") (name "unconnected-(IC9-PJ7-Pad79)") (class "Default")
      (node (ref "IC9") (pin "79") (pinfunction "PJ7_79") (pintype "bidirectional"))
    )
    (net (code "189") (name "unconnected-(P1-PadID)") (class "Default")
      (node (ref "P1") (pin "ID") (pinfunction "ID_ID") (pintype "bidirectional"))
    )
    (net (code "190") (name "unconnected-(P4-NC-Pad1)") (class "Default")
      (node (ref "P4") (pin "1") (pinfunction "NC_1") (pintype "bidirectional"))
    )
    (net (code "191") (name "unconnected-(P4-RSV-Pad8)") (class "Default")
      (node (ref "P4") (pin "8") (pinfunction "RSV_8") (pintype "bidirectional"))
    )
    (net (code "192") (name "unconnected-(RN6-Pad1)") (class "Default")
      (node (ref "RN6") (pin "1") (pinfunction "1_1") (pintype "passive"))
    )
    (net (code "193") (name "unconnected-(RN6A-2-Pad8)") (class "Default")
      (node (ref "RN6") (pin "8") (pinfunction "2_8") (pintype "passive"))
    )
    (net (code "194") (name "unconnected-(RN7-Pad1)") (class "Default")
      (node (ref "RN7") (pin "1") (pinfunction "1_1") (pintype "passive"))
    )
    (net (code "195") (name "unconnected-(RN7A-2-Pad8)") (class "Default")
      (node (ref "RN7") (pin "8") (pinfunction "2_8") (pintype "passive"))
    )
    (net (code "196") (name "unconnected-(RN7C-1-Pad3)") (class "Default")
      (node (ref "RN7") (pin "3") (pinfunction "1_3") (pintype "passive"))
    )
    (net (code "197") (name "unconnected-(RN7C-2-Pad6)") (class "Default")
      (node (ref "RN7") (pin "6") (pinfunction "2_6") (pintype "passive"))
    )
    (net (code "198") (name "unconnected-(RN8D-1-Pad4)") (class "Default")
      (node (ref "RN8") (pin "4") (pinfunction "1_4") (pintype "passive"))
    )
    (net (code "199") (name "unconnected-(RN8D-2-Pad5)") (class "Default")
      (node (ref "RN8") (pin "5") (pinfunction "2_5") (pintype "passive"))
    )
  )
)
